# AJH_tides2_v40.net
KiCad netlist of a schematic drawn in EAGLE
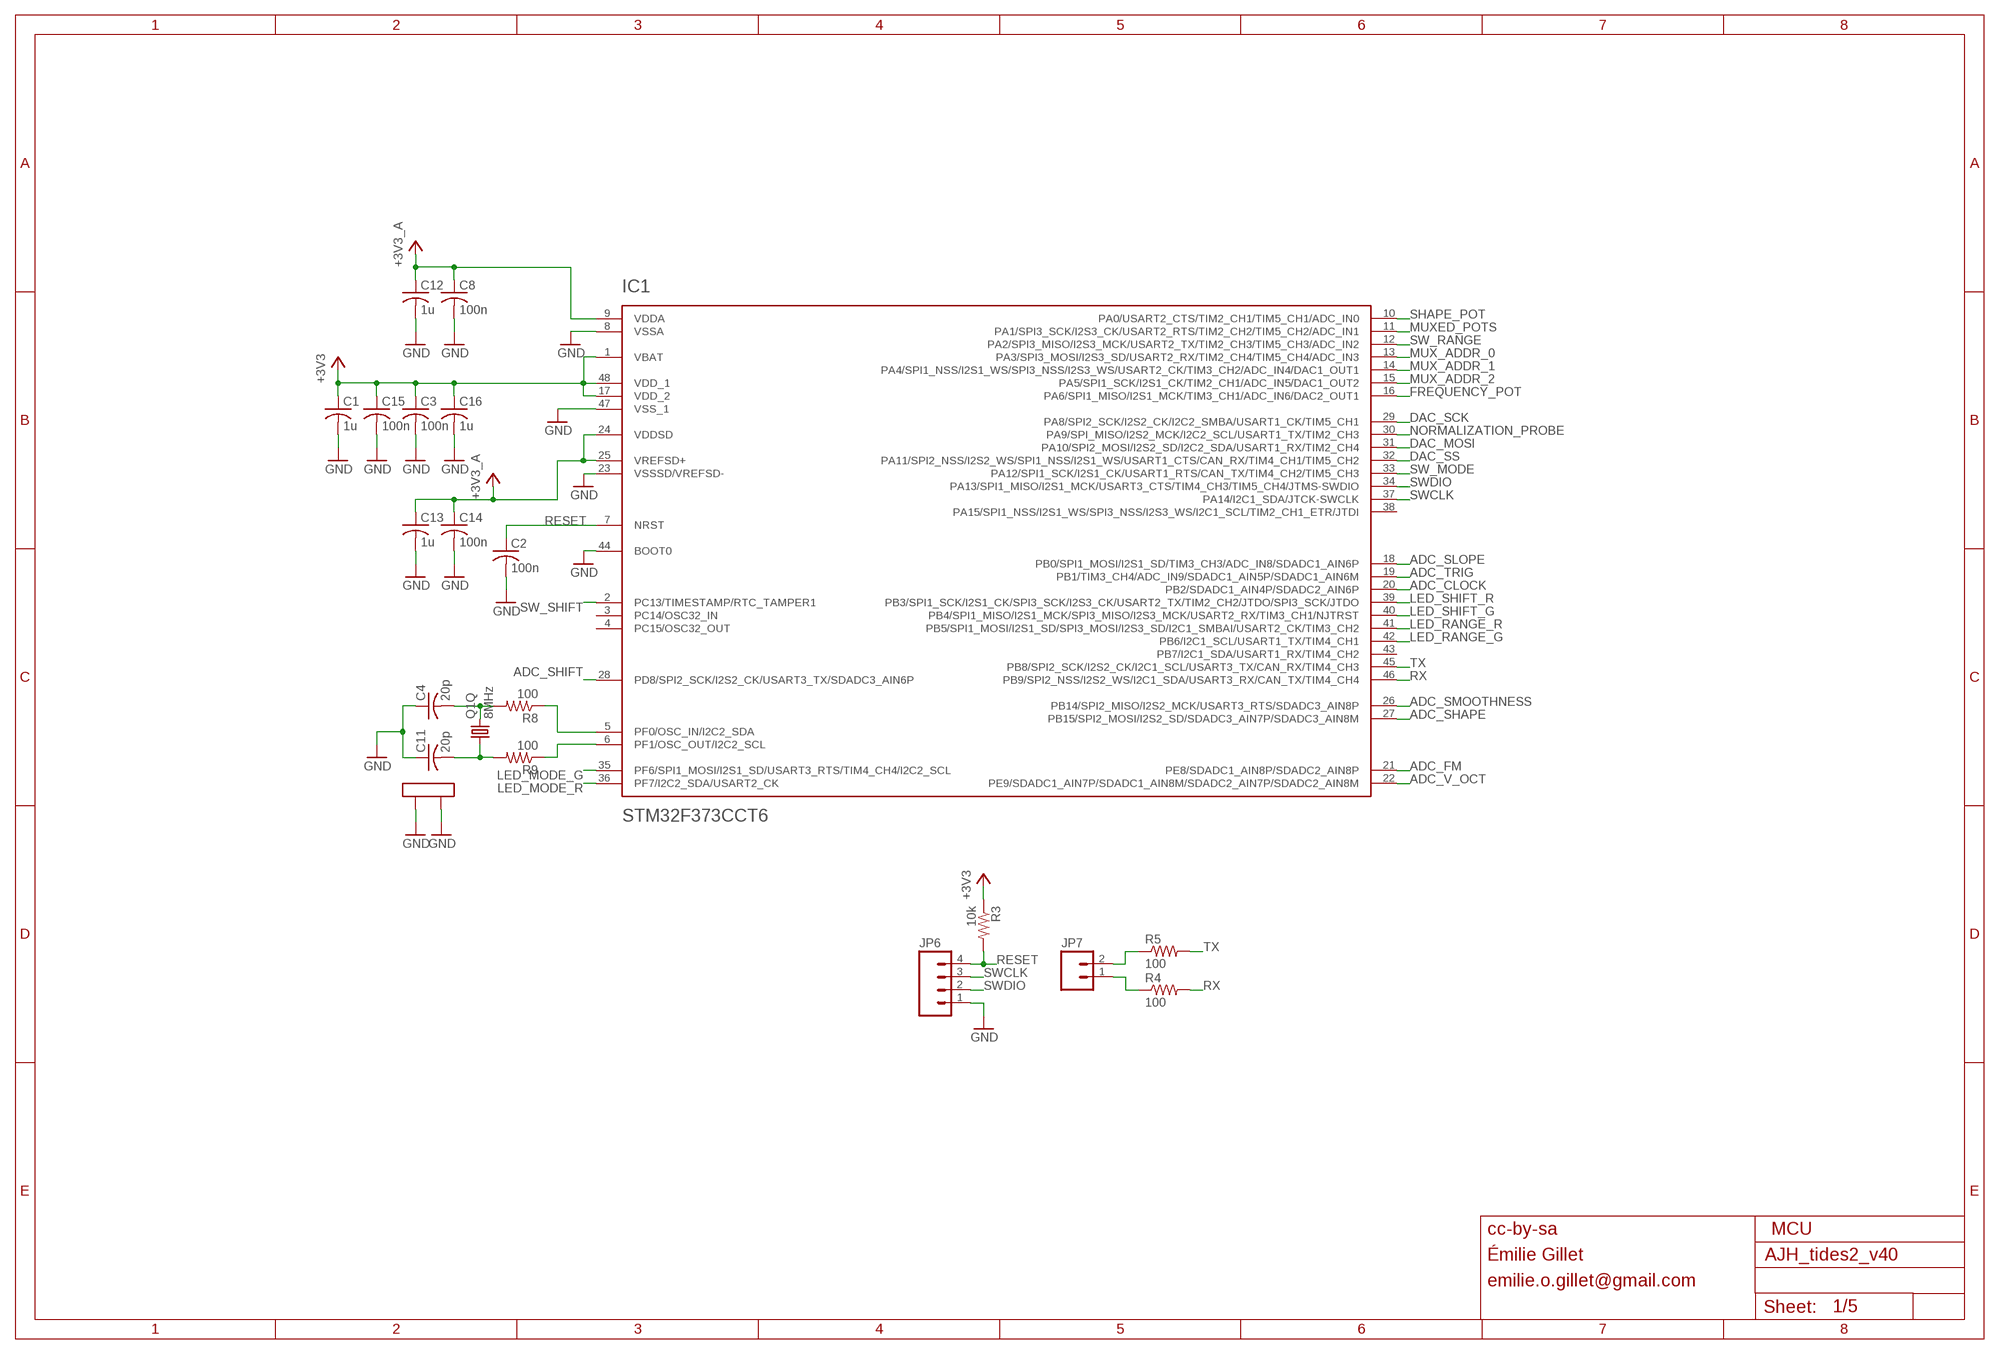
[diagram p0: schematic, sheet 1]
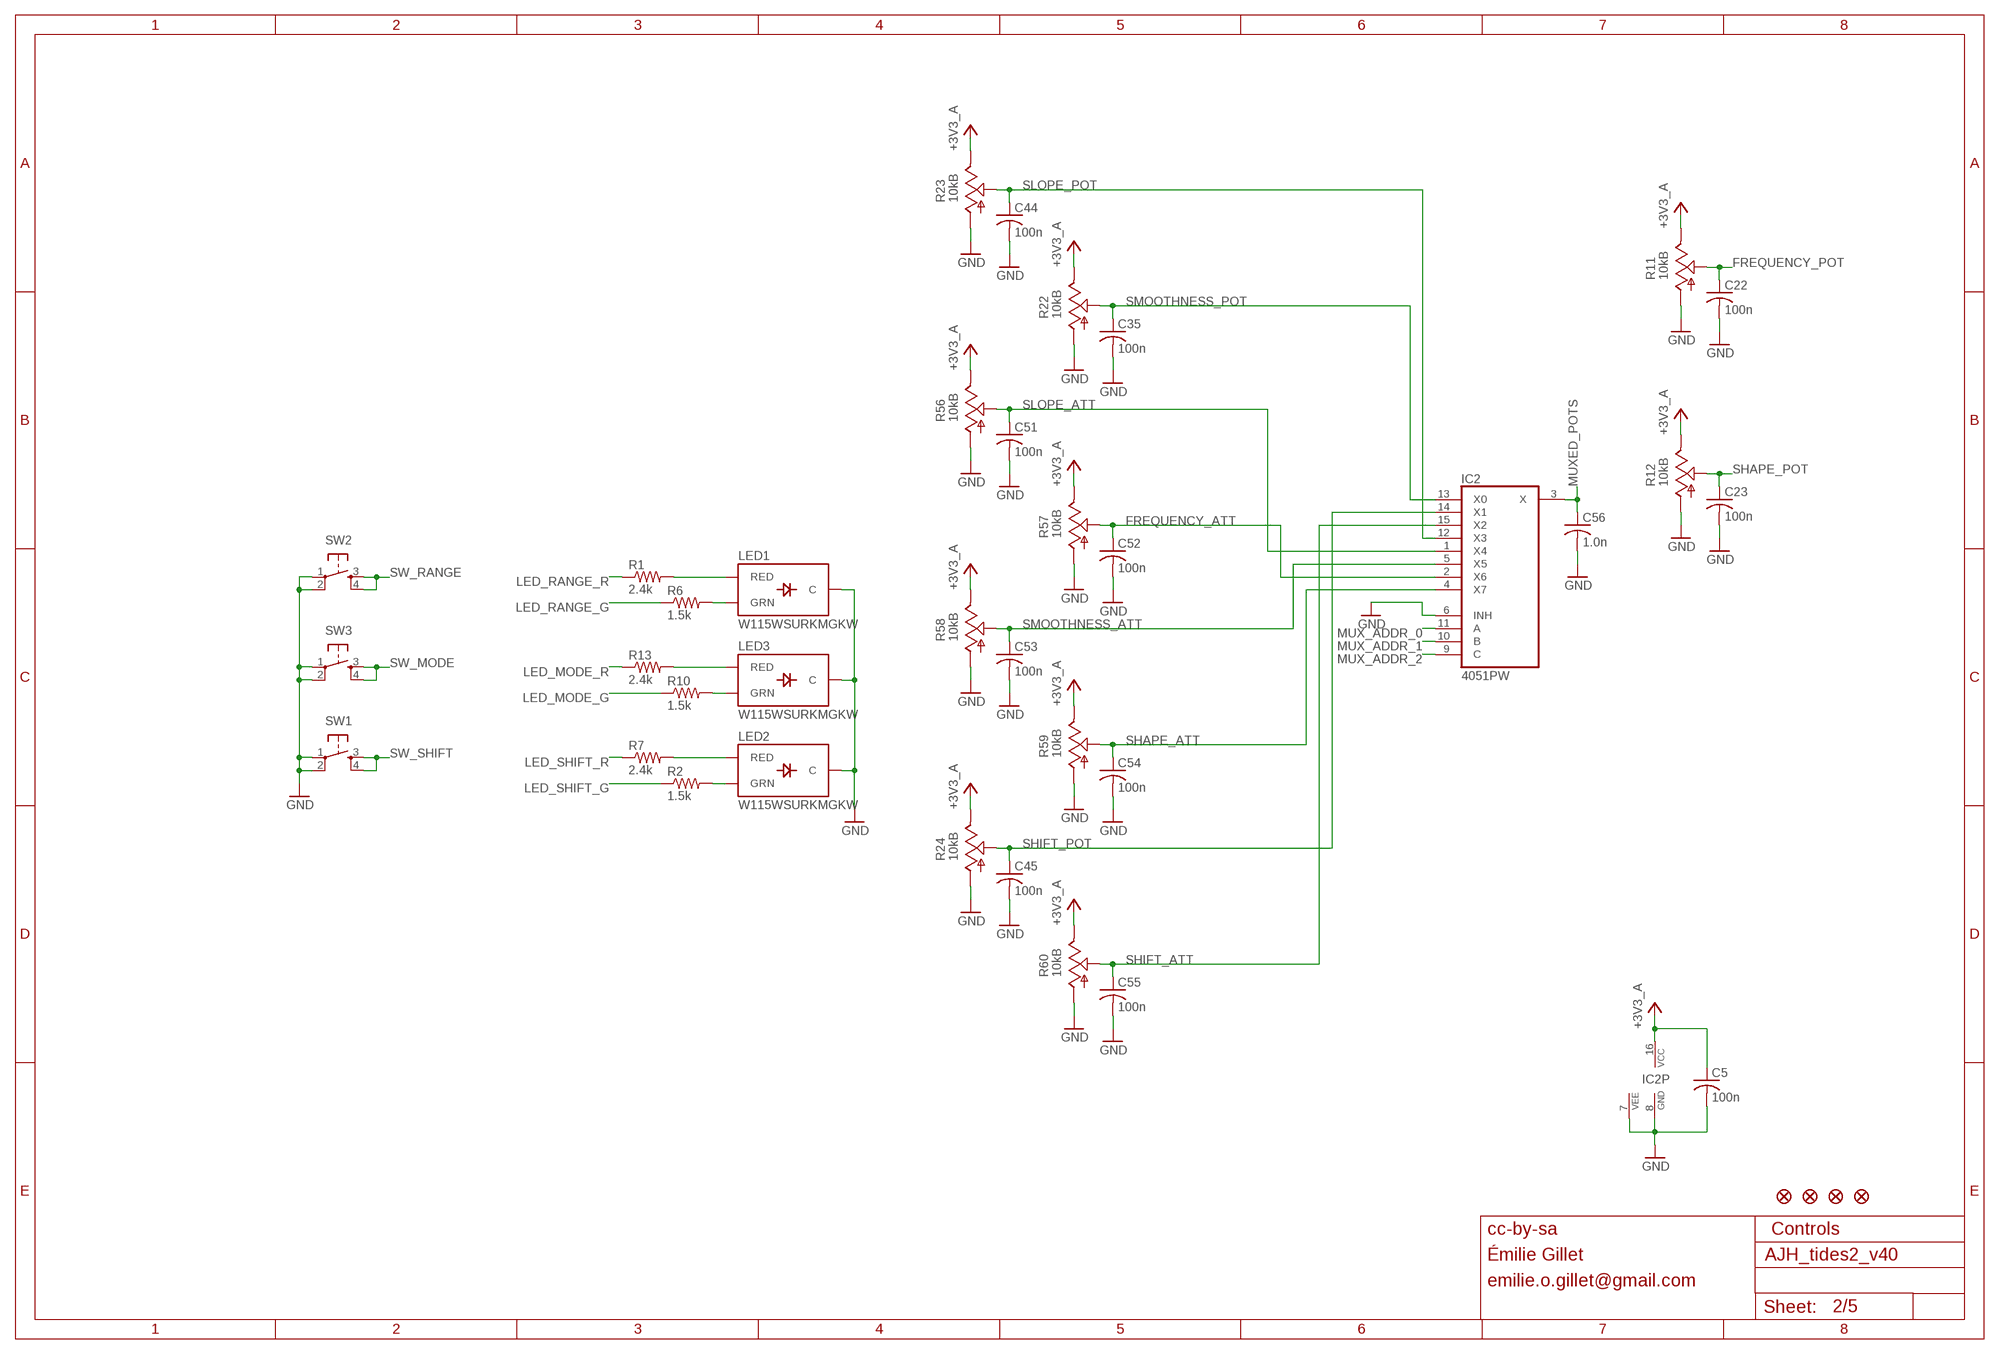
[diagram p1: schematic, sheet 2]
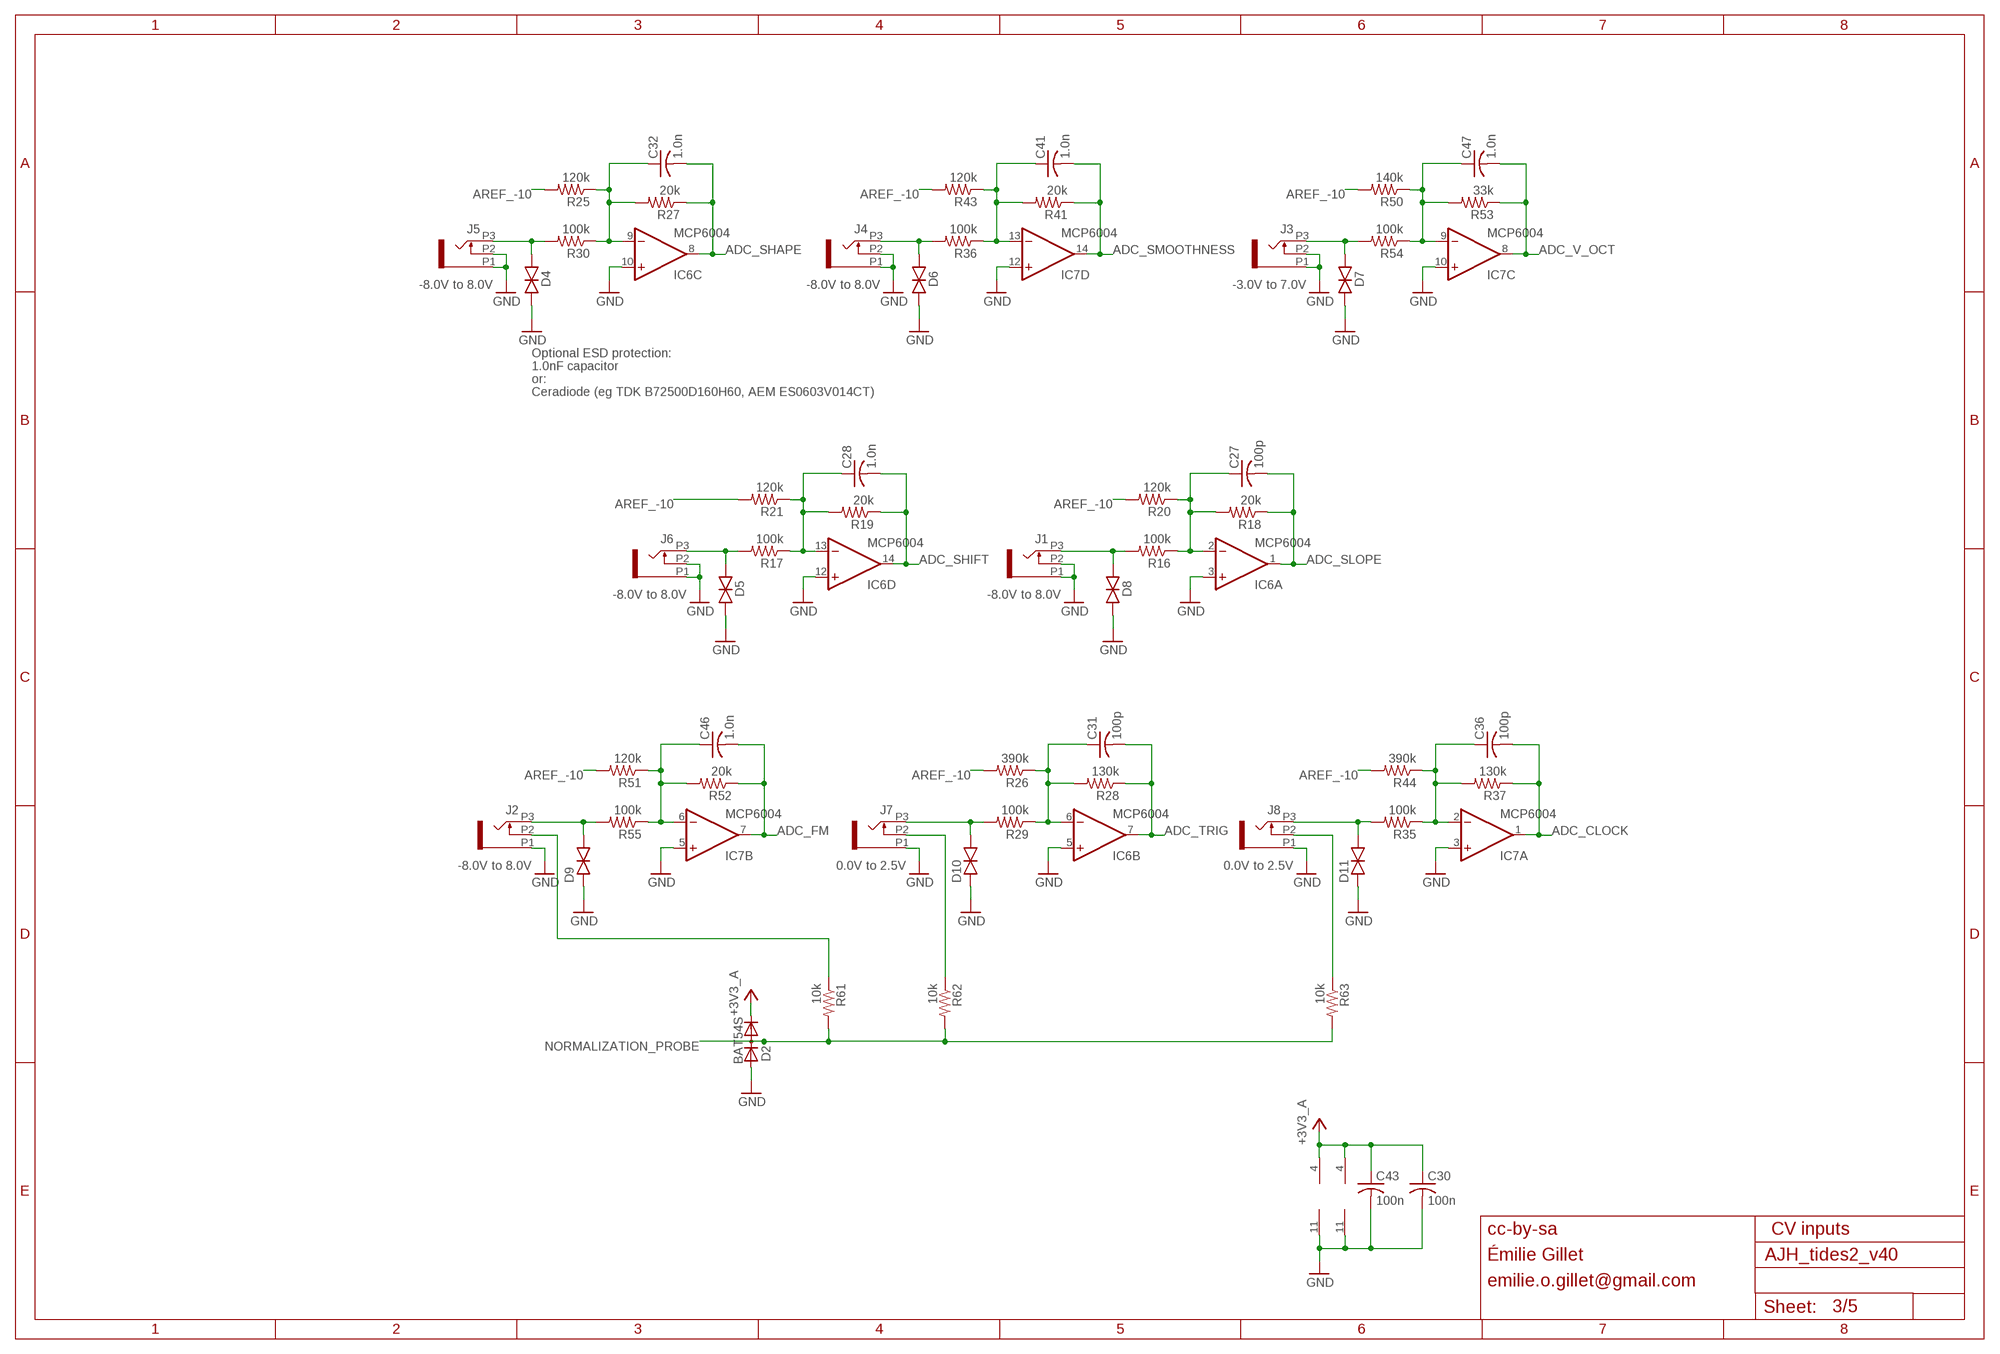
[diagram p2: schematic, sheet 3]
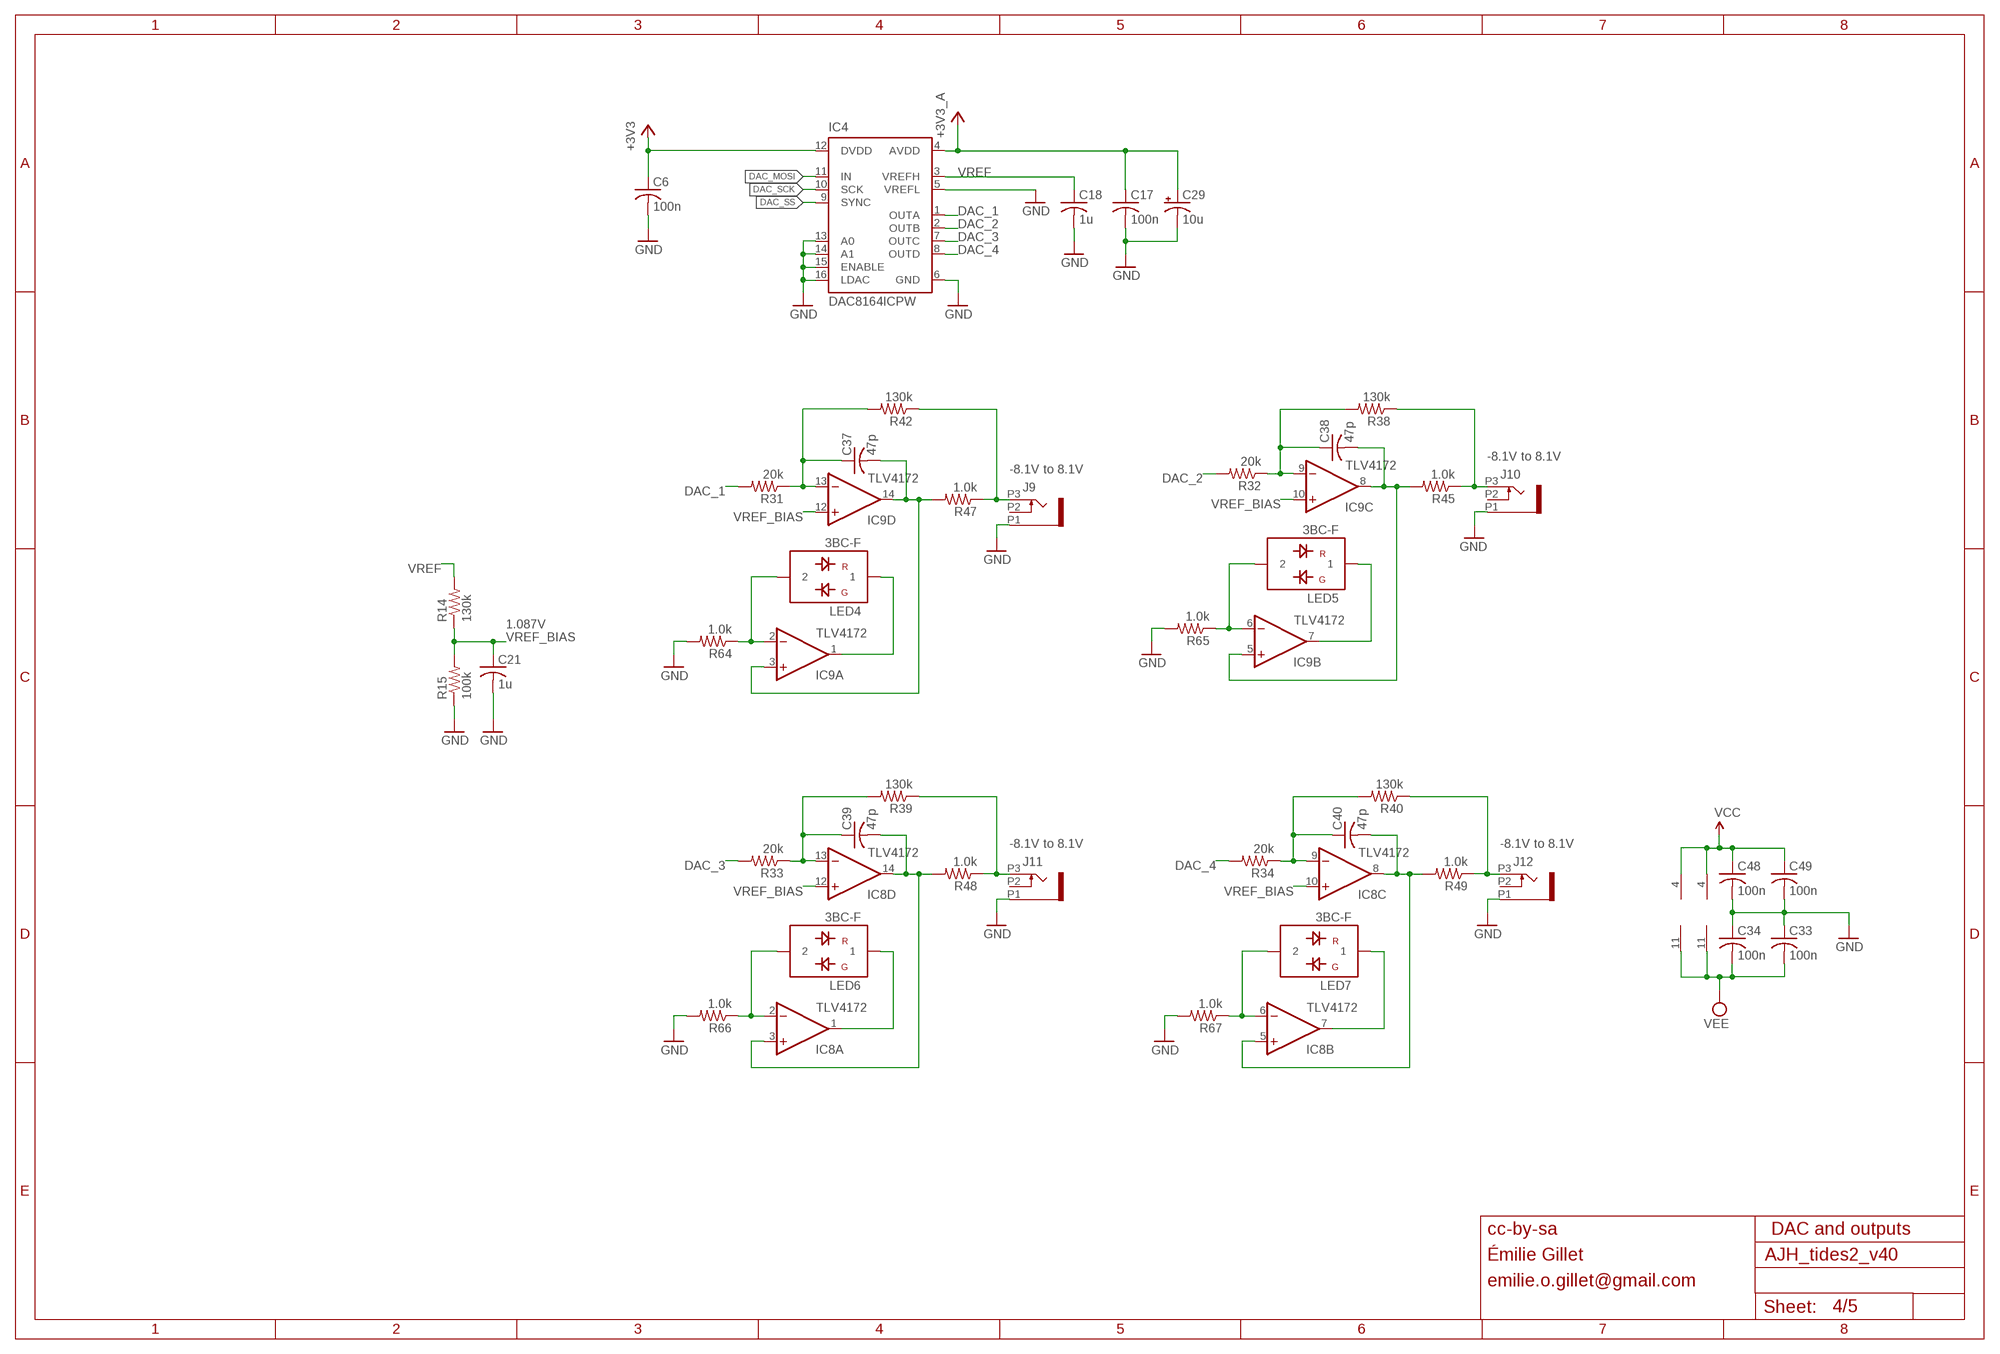
[diagram p3: schematic, sheet 4]
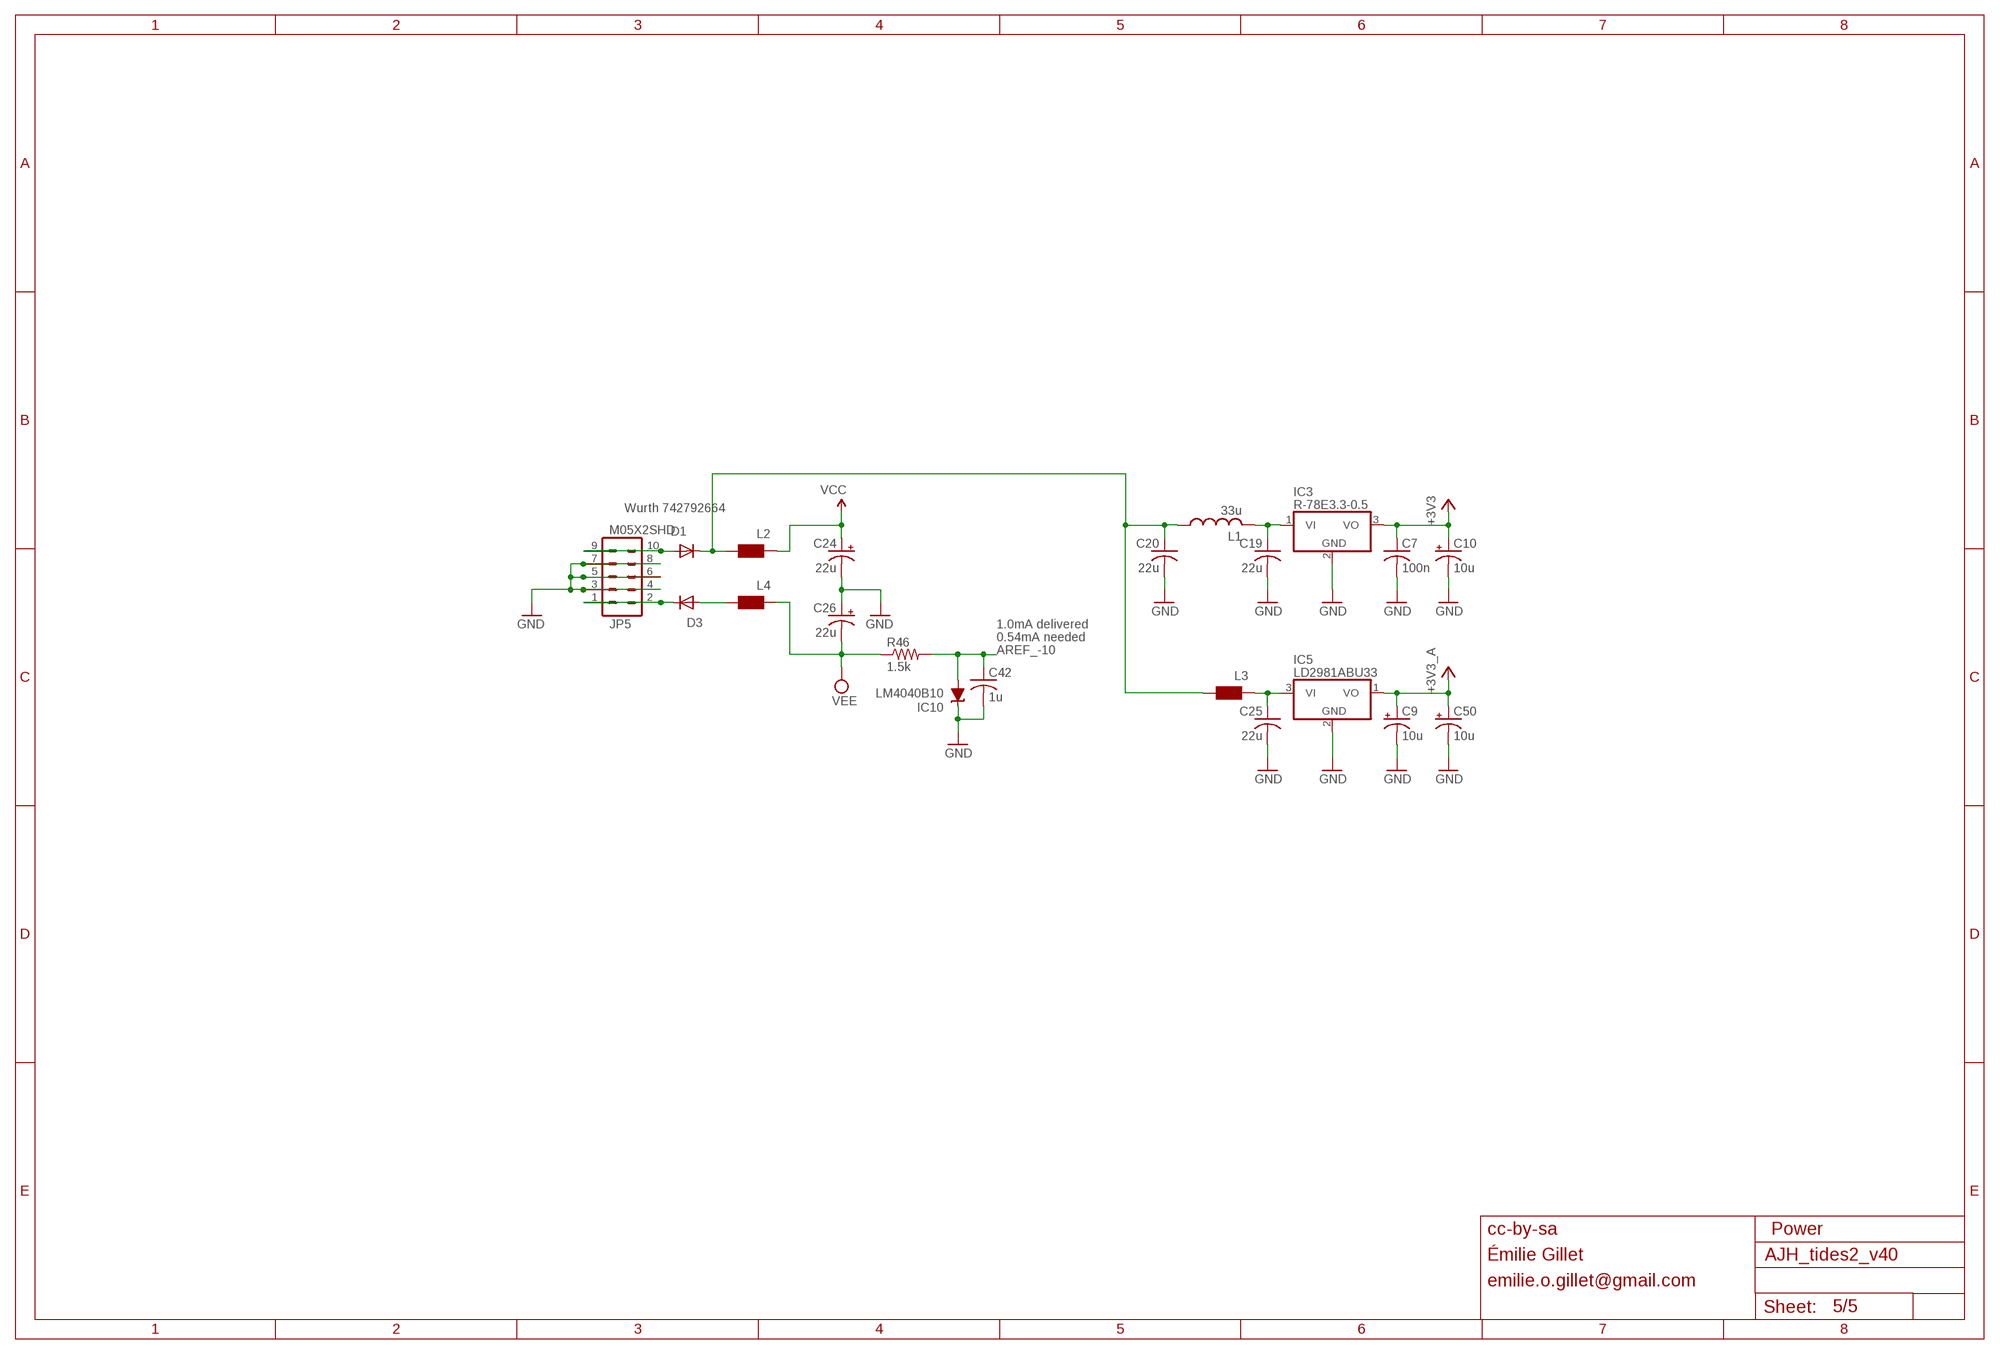
[diagram p4: schematic, sheet 5]

(export (version "E")
  (design (tool "Eeschema 10.0.6"))
  (components
    (comp (ref "C6")
      (value "100n")
      (footprint "eagle-import:C0402")
      (libsource (lib "eagle-import") (part "C-USC0402"))
    )
    (comp (ref "C17")
      (value "100n")
      (footprint "eagle-import:C0402")
      (libsource (lib "eagle-import") (part "C-USC0402"))
    )
    (comp (ref "C18")
      (value "1u")
      (footprint "eagle-import:C0402")
      (libsource (lib "eagle-import") (part "C-USC0402"))
    )
    (comp (ref "C21")
      (value "1u")
      (footprint "eagle-import:C0402")
      (libsource (lib "eagle-import") (part "C-USC0402"))
    )
    (comp (ref "C29")
      (value "10u")
      (footprint "eagle-import:PANASONIC_A")
      (libsource (lib "eagle-import") (part "CPOL-USA"))
    )
    (comp (ref "C33")
      (value "100n")
      (footprint "eagle-import:C0402")
      (libsource (lib "eagle-import") (part "C-USC0402"))
    )
    (comp (ref "C34")
      (value "100n")
      (footprint "eagle-import:C0402")
      (libsource (lib "eagle-import") (part "C-USC0402"))
    )
    (comp (ref "C37")
      (value "47p")
      (footprint "eagle-import:C0402")
      (libsource (lib "eagle-import") (part "C-USC0402"))
    )
    (comp (ref "C38")
      (value "47p")
      (footprint "eagle-import:C0402")
      (libsource (lib "eagle-import") (part "C-USC0402"))
    )
    (comp (ref "C39")
      (value "47p")
      (footprint "eagle-import:C0402")
      (libsource (lib "eagle-import") (part "C-USC0402"))
    )
    (comp (ref "C40")
      (value "47p")
      (footprint "eagle-import:C0402")
      (libsource (lib "eagle-import") (part "C-USC0402"))
    )
    (comp (ref "C48")
      (value "100n")
      (footprint "eagle-import:C0402")
      (libsource (lib "eagle-import") (part "C-USC0402"))
    )
    (comp (ref "C49")
      (value "100n")
      (footprint "eagle-import:C0402")
      (libsource (lib "eagle-import") (part "C-USC0402"))
    )
    (comp (ref "IC4")
      (value "DAC8164ICPW")
      (footprint "eagle-import:SOP65P640X110-16N")
      (libsource (lib "eagle-import") (part "DAC8564"))
    )
    (comp (ref "IC8")
      (value "TLV4172")
      (footprint "eagle-import:TSSOP14_065")
      (libsource (lib "eagle-import") (part "TL074PW"))
    )
    (comp (ref "IC9")
      (value "TLV4172")
      (footprint "eagle-import:TSSOP14_065")
      (libsource (lib "eagle-import") (part "TL074PW"))
    )
    (comp (ref "J9")
      (value "PJ301_THONKICONN6")
      (footprint "eagle-import:WQP_PJ_301M6")
      (libsource (lib "eagle-import") (part "PJ301_THONKICONN6"))
    )
    (comp (ref "J10")
      (value "PJ301_THONKICONN6")
      (footprint "eagle-import:WQP_PJ_301M6")
      (libsource (lib "eagle-import") (part "PJ301_THONKICONN6"))
    )
    (comp (ref "J11")
      (value "PJ301_THONKICONN6")
      (footprint "eagle-import:WQP_PJ_301M6")
      (libsource (lib "eagle-import") (part "PJ301_THONKICONN6"))
    )
    (comp (ref "J12")
      (value "PJ301_THONKICONN6")
      (footprint "eagle-import:WQP_PJ_301M6")
      (libsource (lib "eagle-import") (part "PJ301_THONKICONN6"))
    )
    (comp (ref "LED4")
      (value "3BC-F")
      (footprint "eagle-import:LED3MM")
      (libsource (lib "eagle-import") (part "LED-BICOLOR-SHARED-THROUGHHOLE"))
    )
    (comp (ref "LED5")
      (value "3BC-F")
      (footprint "eagle-import:LED3MM")
      (libsource (lib "eagle-import") (part "LED-BICOLOR-SHARED-THROUGHHOLE"))
    )
    (comp (ref "LED6")
      (value "3BC-F")
      (footprint "eagle-import:LED3MM")
      (libsource (lib "eagle-import") (part "LED-BICOLOR-SHARED-THROUGHHOLE"))
    )
    (comp (ref "LED7")
      (value "3BC-F")
      (footprint "eagle-import:LED3MM")
      (libsource (lib "eagle-import") (part "LED-BICOLOR-SHARED-THROUGHHOLE"))
    )
    (comp (ref "R14")
      (value "130k")
      (footprint "eagle-import:R0402")
      (libsource (lib "eagle-import") (part "R-US_R0402"))
    )
    (comp (ref "R15")
      (value "100k")
      (footprint "eagle-import:R0402")
      (libsource (lib "eagle-import") (part "R-US_R0402"))
    )
    (comp (ref "R31")
      (value "20k")
      (footprint "eagle-import:R0402")
      (libsource (lib "eagle-import") (part "R-US_R0402"))
    )
    (comp (ref "R32")
      (value "20k")
      (footprint "eagle-import:R0402")
      (libsource (lib "eagle-import") (part "R-US_R0402"))
    )
    (comp (ref "R33")
      (value "20k")
      (footprint "eagle-import:R0402")
      (libsource (lib "eagle-import") (part "R-US_R0402"))
    )
    (comp (ref "R34")
      (value "20k")
      (footprint "eagle-import:R0402")
      (libsource (lib "eagle-import") (part "R-US_R0402"))
    )
    (comp (ref "R38")
      (value "130k")
      (footprint "eagle-import:R0402")
      (libsource (lib "eagle-import") (part "R-US_R0402"))
    )
    (comp (ref "R39")
      (value "130k")
      (footprint "eagle-import:R0402")
      (libsource (lib "eagle-import") (part "R-US_R0402"))
    )
    (comp (ref "R40")
      (value "130k")
      (footprint "eagle-import:R0402")
      (libsource (lib "eagle-import") (part "R-US_R0402"))
    )
    (comp (ref "R42")
      (value "130k")
      (footprint "eagle-import:R0402")
      (libsource (lib "eagle-import") (part "R-US_R0402"))
    )
    (comp (ref "R45")
      (value "1.0k")
      (footprint "eagle-import:R0603")
      (libsource (lib "eagle-import") (part "R-US_R0603"))
    )
    (comp (ref "R47")
      (value "1.0k")
      (footprint "eagle-import:R0603")
      (libsource (lib "eagle-import") (part "R-US_R0603"))
    )
    (comp (ref "R48")
      (value "1.0k")
      (footprint "eagle-import:R0603")
      (libsource (lib "eagle-import") (part "R-US_R0603"))
    )
    (comp (ref "R49")
      (value "1.0k")
      (footprint "eagle-import:R0603")
      (libsource (lib "eagle-import") (part "R-US_R0603"))
    )
    (comp (ref "R64")
      (value "1.0k")
      (footprint "eagle-import:R0402")
      (libsource (lib "eagle-import") (part "R-US_R0402"))
    )
    (comp (ref "R65")
      (value "1.0k")
      (footprint "eagle-import:R0402")
      (libsource (lib "eagle-import") (part "R-US_R0402"))
    )
    (comp (ref "R66")
      (value "1.0k")
      (footprint "eagle-import:R0402")
      (libsource (lib "eagle-import") (part "R-US_R0402"))
    )
    (comp (ref "R67")
      (value "1.0k")
      (footprint "eagle-import:R0402")
      (libsource (lib "eagle-import") (part "R-US_R0402"))
    )
    (comp (ref "C7")
      (value "100n")
      (footprint "eagle-import:C0402")
      (libsource (lib "eagle-import") (part "C-USC0402"))
    )
    (comp (ref "C9")
      (value "10u")
      (footprint "eagle-import:PANASONIC_A")
      (libsource (lib "eagle-import") (part "CPOL-USA"))
    )
    (comp (ref "C10")
      (value "10u")
      (footprint "eagle-import:PANASONIC_A")
      (libsource (lib "eagle-import") (part "CPOL-USA"))
    )
    (comp (ref "C19")
      (value "22u")
      (footprint "eagle-import:C1206")
      (libsource (lib "eagle-import") (part "C-USC1206"))
    )
    (comp (ref "C20")
      (value "22u")
      (footprint "eagle-import:C1206")
      (libsource (lib "eagle-import") (part "C-USC1206"))
    )
    (comp (ref "C24")
      (value "22u")
      (footprint "eagle-import:PANASONIC_B")
      (libsource (lib "eagle-import") (part "CPOL-USB"))
    )
    (comp (ref "C25")
      (value "22u")
      (footprint "eagle-import:C1206")
      (libsource (lib "eagle-import") (part "C-USC1206"))
    )
    (comp (ref "C26")
      (value "22u")
      (footprint "eagle-import:PANASONIC_B")
      (libsource (lib "eagle-import") (part "CPOL-USB"))
    )
    (comp (ref "C42")
      (value "1u")
      (footprint "eagle-import:C0402")
      (libsource (lib "eagle-import") (part "C-USC0402"))
    )
    (comp (ref "C50")
      (value "10u")
      (footprint "eagle-import:PANASONIC_A")
      (libsource (lib "eagle-import") (part "CPOL-USA"))
    )
    (comp (ref "D1")
      (value "1N5819HW")
      (footprint "eagle-import:SOD123")
      (libsource (lib "eagle-import") (part "DIODE-SOD123"))
    )
    (comp (ref "D3")
      (value "1N5819HW")
      (footprint "eagle-import:SOD123")
      (libsource (lib "eagle-import") (part "DIODE-SOD123"))
    )
    (comp (ref "IC3")
      (value "R-78E3.3-0.5")
      (footprint "eagle-import:WE78")
      (libsource (lib "eagle-import") (part "WE173950378"))
    )
    (comp (ref "IC5")
      (value "LD2981ABU33")
      (footprint "eagle-import:SOT89")
      (libsource (lib "eagle-import") (part "LD2981ABU"))
    )
    (comp (ref "IC10")
      (value "LM4040B10")
      (footprint "eagle-import:DBZ_R-PDSO-G3")
      (libsource (lib "eagle-import") (part "LM4041DBZB12"))
    )
    (comp (ref "JP5")
      (value "M05X2SHD")
      (footprint "eagle-import:2X5-SHROUDED")
      (libsource (lib "eagle-import") (part "M05X2SHD"))
    )
    (comp (ref "L1")
      (value "33u")
      (footprint "eagle-import:L2012C")
      (libsource (lib "eagle-import") (part "L-USL2012C"))
    )
    (comp (ref "L2")
      (value "WE-CBF_0603")
      (footprint "eagle-import:0603")
      (libsource (lib "eagle-import") (part "WE-CBF_0603"))
    )
    (comp (ref "L3")
      (value "WE-CBF_0603")
      (footprint "eagle-import:0603")
      (libsource (lib "eagle-import") (part "WE-CBF_0603"))
    )
    (comp (ref "L4")
      (value "WE-CBF_0603")
      (footprint "eagle-import:0603")
      (libsource (lib "eagle-import") (part "WE-CBF_0603"))
    )
    (comp (ref "R46")
      (value "1.5k")
      (footprint "eagle-import:R0402")
      (libsource (lib "eagle-import") (part "R-US_R0402"))
    )
    (comp (ref "C27")
      (value "100p")
      (footprint "eagle-import:C0402")
      (libsource (lib "eagle-import") (part "C-USC0402"))
    )
    (comp (ref "C28")
      (value "1.0n")
      (footprint "eagle-import:C0402")
      (libsource (lib "eagle-import") (part "C-USC0402"))
    )
    (comp (ref "C30")
      (value "100n")
      (footprint "eagle-import:C0402")
      (libsource (lib "eagle-import") (part "C-USC0402"))
    )
    (comp (ref "C31")
      (value "100p")
      (footprint "eagle-import:C0402")
      (libsource (lib "eagle-import") (part "C-USC0402"))
    )
    (comp (ref "C32")
      (value "1.0n")
      (footprint "eagle-import:C0402")
      (libsource (lib "eagle-import") (part "C-USC0402"))
    )
    (comp (ref "C36")
      (value "100p")
      (footprint "eagle-import:C0402")
      (libsource (lib "eagle-import") (part "C-USC0402"))
    )
    (comp (ref "C41")
      (value "1.0n")
      (footprint "eagle-import:C0402")
      (libsource (lib "eagle-import") (part "C-USC0402"))
    )
    (comp (ref "C43")
      (value "100n")
      (footprint "eagle-import:C0402")
      (libsource (lib "eagle-import") (part "C-USC0402"))
    )
    (comp (ref "C46")
      (value "1.0n")
      (footprint "eagle-import:C0402")
      (libsource (lib "eagle-import") (part "C-USC0402"))
    )
    (comp (ref "C47")
      (value "1.0n")
      (footprint "eagle-import:C0402")
      (libsource (lib "eagle-import") (part "C-USC0402"))
    )
    (comp (ref "D2")
      (value "BAT54S")
      (footprint "eagle-import:SOT23")
      (libsource (lib "eagle-import") (part "DIODE_2CACA-SOT23"))
    )
    (comp (ref "D4")
      (value "TVS")
      (footprint "eagle-import:0603")
      (libsource (lib "eagle-import") (part "TVS"))
    )
    (comp (ref "D5")
      (value "TVS")
      (footprint "eagle-import:0603")
      (libsource (lib "eagle-import") (part "TVS"))
    )
    (comp (ref "D6")
      (value "TVS")
      (footprint "eagle-import:0603")
      (libsource (lib "eagle-import") (part "TVS"))
    )
    (comp (ref "D7")
      (value "TVS")
      (footprint "eagle-import:0603")
      (libsource (lib "eagle-import") (part "TVS"))
    )
    (comp (ref "D8")
      (value "TVS")
      (footprint "eagle-import:0603")
      (libsource (lib "eagle-import") (part "TVS"))
    )
    (comp (ref "D9")
      (value "TVS")
      (footprint "eagle-import:0603")
      (libsource (lib "eagle-import") (part "TVS"))
    )
    (comp (ref "D10")
      (value "TVS")
      (footprint "eagle-import:0603")
      (libsource (lib "eagle-import") (part "TVS"))
    )
    (comp (ref "D11")
      (value "TVS")
      (footprint "eagle-import:0603")
      (libsource (lib "eagle-import") (part "TVS"))
    )
    (comp (ref "IC6")
      (value "MCP6004")
      (footprint "eagle-import:TSSOP14_065")
      (libsource (lib "eagle-import") (part "TL074PW"))
    )
    (comp (ref "IC7")
      (value "MCP6004")
      (footprint "eagle-import:TSSOP14_065")
      (libsource (lib "eagle-import") (part "TL074PW"))
    )
    (comp (ref "J1")
      (value "PJ301_THONKICONN6")
      (footprint "eagle-import:WQP_PJ_301M6")
      (libsource (lib "eagle-import") (part "og-pj301_variations_PJ301_THONKICONN6"))
    )
    (comp (ref "J2")
      (value "PJ301_THONKICONN6")
      (footprint "eagle-import:WQP_PJ_301M6")
      (libsource (lib "eagle-import") (part "og-pj301_variations_PJ301_THONKICONN6"))
    )
    (comp (ref "J3")
      (value "PJ301_THONKICONN6")
      (footprint "eagle-import:WQP_PJ_301M6")
      (libsource (lib "eagle-import") (part "og-pj301_variations_PJ301_THONKICONN6"))
    )
    (comp (ref "J4")
      (value "PJ301_THONKICONN6")
      (footprint "eagle-import:WQP_PJ_301M6")
      (libsource (lib "eagle-import") (part "og-pj301_variations_PJ301_THONKICONN6"))
    )
    (comp (ref "J5")
      (value "PJ301_THONKICONN6")
      (footprint "eagle-import:WQP_PJ_301M6")
      (libsource (lib "eagle-import") (part "og-pj301_variations_PJ301_THONKICONN6"))
    )
    (comp (ref "J6")
      (value "PJ301_THONKICONN6")
      (footprint "eagle-import:WQP_PJ_301M6")
      (libsource (lib "eagle-import") (part "og-pj301_variations_PJ301_THONKICONN6"))
    )
    (comp (ref "J7")
      (value "PJ301_THONKICONN6")
      (footprint "eagle-import:WQP_PJ_301M6")
      (libsource (lib "eagle-import") (part "og-pj301_variations_PJ301_THONKICONN6"))
    )
    (comp (ref "J8")
      (value "PJ301_THONKICONN6")
      (footprint "eagle-import:WQP_PJ_301M6")
      (libsource (lib "eagle-import") (part "og-pj301_variations_PJ301_THONKICONN6"))
    )
    (comp (ref "R16")
      (value "100k")
      (footprint "eagle-import:R0402")
      (libsource (lib "eagle-import") (part "R-US_R0402"))
    )
    (comp (ref "R17")
      (value "100k")
      (footprint "eagle-import:R0402")
      (libsource (lib "eagle-import") (part "R-US_R0402"))
    )
    (comp (ref "R18")
      (value "20k")
      (footprint "eagle-import:R0402")
      (libsource (lib "eagle-import") (part "R-US_R0402"))
    )
    (comp (ref "R19")
      (value "20k")
      (footprint "eagle-import:R0402")
      (libsource (lib "eagle-import") (part "R-US_R0402"))
    )
    (comp (ref "R20")
      (value "120k")
      (footprint "eagle-import:R0402")
      (libsource (lib "eagle-import") (part "R-US_R0402"))
    )
    (comp (ref "R21")
      (value "120k")
      (footprint "eagle-import:R0402")
      (libsource (lib "eagle-import") (part "R-US_R0402"))
    )
    (comp (ref "R25")
      (value "120k")
      (footprint "eagle-import:R0402")
      (libsource (lib "eagle-import") (part "R-US_R0402"))
    )
    (comp (ref "R26")
      (value "390k")
      (footprint "eagle-import:R0402")
      (libsource (lib "eagle-import") (part "R-US_R0402"))
    )
    (comp (ref "R27")
      (value "20k")
      (footprint "eagle-import:R0402")
      (libsource (lib "eagle-import") (part "R-US_R0402"))
    )
    (comp (ref "R28")
      (value "130k")
      (footprint "eagle-import:R0402")
      (libsource (lib "eagle-import") (part "R-US_R0402"))
    )
    (comp (ref "R29")
      (value "100k")
      (footprint "eagle-import:R0402")
      (libsource (lib "eagle-import") (part "R-US_R0402"))
    )
    (comp (ref "R30")
      (value "100k")
      (footprint "eagle-import:R0402")
      (libsource (lib "eagle-import") (part "R-US_R0402"))
    )
    (comp (ref "R35")
      (value "100k")
      (footprint "eagle-import:R0402")
      (libsource (lib "eagle-import") (part "R-US_R0402"))
    )
    (comp (ref "R36")
      (value "100k")
      (footprint "eagle-import:R0402")
      (libsource (lib "eagle-import") (part "R-US_R0402"))
    )
    (comp (ref "R37")
      (value "130k")
      (footprint "eagle-import:R0402")
      (libsource (lib "eagle-import") (part "R-US_R0402"))
    )
    (comp (ref "R41")
      (value "20k")
      (footprint "eagle-import:R0402")
      (libsource (lib "eagle-import") (part "R-US_R0402"))
    )
    (comp (ref "R43")
      (value "120k")
      (footprint "eagle-import:R0402")
      (libsource (lib "eagle-import") (part "R-US_R0402"))
    )
    (comp (ref "R44")
      (value "390k")
      (footprint "eagle-import:R0402")
      (libsource (lib "eagle-import") (part "R-US_R0402"))
    )
    (comp (ref "R50")
      (value "140k")
      (footprint "eagle-import:R0402")
      (libsource (lib "eagle-import") (part "R-US_R0402"))
    )
    (comp (ref "R51")
      (value "120k")
      (footprint "eagle-import:R0402")
      (libsource (lib "eagle-import") (part "R-US_R0402"))
    )
    (comp (ref "R52")
      (value "20k")
      (footprint "eagle-import:R0402")
      (libsource (lib "eagle-import") (part "R-US_R0402"))
    )
    (comp (ref "R53")
      (value "33k")
      (footprint "eagle-import:R0402")
      (libsource (lib "eagle-import") (part "R-US_R0402"))
    )
    (comp (ref "R54")
      (value "100k")
      (footprint "eagle-import:R0402")
      (libsource (lib "eagle-import") (part "R-US_R0402"))
    )
    (comp (ref "R55")
      (value "100k")
      (footprint "eagle-import:R0402")
      (libsource (lib "eagle-import") (part "R-US_R0402"))
    )
    (comp (ref "R61")
      (value "10k")
      (footprint "eagle-import:R0402")
      (libsource (lib "eagle-import") (part "R-US_R0402"))
    )
    (comp (ref "R62")
      (value "10k")
      (footprint "eagle-import:R0402")
      (libsource (lib "eagle-import") (part "R-US_R0402"))
    )
    (comp (ref "R63")
      (value "10k")
      (footprint "eagle-import:R0402")
      (libsource (lib "eagle-import") (part "R-US_R0402"))
    )
    (comp (ref "C5")
      (value "100n")
      (footprint "eagle-import:C0402")
      (libsource (lib "eagle-import") (part "C-USC0402"))
    )
    (comp (ref "C22")
      (value "100n")
      (footprint "eagle-import:C0402")
      (libsource (lib "eagle-import") (part "C-USC0402"))
    )
    (comp (ref "C23")
      (value "100n")
      (footprint "eagle-import:C0402")
      (libsource (lib "eagle-import") (part "C-USC0402"))
    )
    (comp (ref "C35")
      (value "100n")
      (footprint "eagle-import:C0402")
      (libsource (lib "eagle-import") (part "C-USC0402"))
    )
    (comp (ref "C44")
      (value "100n")
      (footprint "eagle-import:C0402")
      (libsource (lib "eagle-import") (part "C-USC0402"))
    )
    (comp (ref "C45")
      (value "100n")
      (footprint "eagle-import:C0402")
      (libsource (lib "eagle-import") (part "C-USC0402"))
    )
    (comp (ref "C51")
      (value "100n")
      (footprint "eagle-import:C0402")
      (libsource (lib "eagle-import") (part "C-USC0402"))
    )
    (comp (ref "C52")
      (value "100n")
      (footprint "eagle-import:C0402")
      (libsource (lib "eagle-import") (part "C-USC0402"))
    )
    (comp (ref "C53")
      (value "100n")
      (footprint "eagle-import:C0402")
      (libsource (lib "eagle-import") (part "C-USC0402"))
    )
    (comp (ref "C54")
      (value "100n")
      (footprint "eagle-import:C0402")
      (libsource (lib "eagle-import") (part "C-USC0402"))
    )
    (comp (ref "C55")
      (value "100n")
      (footprint "eagle-import:C0402")
      (libsource (lib "eagle-import") (part "C-USC0402"))
    )
    (comp (ref "C56")
      (value "1.0n")
      (footprint "eagle-import:C0402")
      (libsource (lib "eagle-import") (part "C-USC0402"))
    )
    (comp (ref "IC2")
      (value "4051PW")
      (footprint "eagle-import:TSSOP16_065")
      (libsource (lib "eagle-import") (part "4051PW"))
    )
    (comp (ref "JP1")
      (value "FIDUCIAL1X2")
      (footprint "eagle-import:FIDUCIAL-1X2")
      (libsource (lib "eagle-import") (part "FIDUCIAL1X2"))
    )
    (comp (ref "JP2")
      (value "FIDUCIAL1X2")
      (footprint "eagle-import:FIDUCIAL-1X2")
      (libsource (lib "eagle-import") (part "FIDUCIAL1X2"))
    )
    (comp (ref "JP3")
      (value "FIDUCIAL1X2")
      (footprint "eagle-import:FIDUCIAL-1X2")
      (libsource (lib "eagle-import") (part "FIDUCIAL1X2"))
    )
    (comp (ref "JP4")
      (value "FIDUCIAL1X2")
      (footprint "eagle-import:FIDUCIAL-1X2")
      (libsource (lib "eagle-import") (part "FIDUCIAL1X2"))
    )
    (comp (ref "LED1")
      (value "W115WSURKMGKW")
      (footprint "eagle-import:LED-BICOLOR-THROUGHHOLE-2.54")
      (libsource (lib "eagle-import") (part "LED-BICOLOR-THROUGHHOLE2.54"))
    )
    (comp (ref "LED2")
      (value "W115WSURKMGKW")
      (footprint "eagle-import:LED-BICOLOR-THROUGHHOLE-2.54")
      (libsource (lib "eagle-import") (part "LED-BICOLOR-THROUGHHOLE2.54"))
    )
    (comp (ref "LED3")
      (value "W115WSURKMGKW")
      (footprint "eagle-import:LED-BICOLOR-THROUGHHOLE-2.54")
      (libsource (lib "eagle-import") (part "LED-BICOLOR-THROUGHHOLE2.54"))
    )
    (comp (ref "R1")
      (value "2.4k")
      (footprint "eagle-import:R0402")
      (libsource (lib "eagle-import") (part "R-US_R0402"))
    )
    (comp (ref "R2")
      (value "1.5k")
      (footprint "eagle-import:R0402")
      (libsource (lib "eagle-import") (part "R-US_R0402"))
    )
    (comp (ref "R6")
      (value "1.5k")
      (footprint "eagle-import:R0402")
      (libsource (lib "eagle-import") (part "R-US_R0402"))
    )
    (comp (ref "R7")
      (value "2.4k")
      (footprint "eagle-import:R0402")
      (libsource (lib "eagle-import") (part "R-US_R0402"))
    )
    (comp (ref "R10")
      (value "1.5k")
      (footprint "eagle-import:R0402")
      (libsource (lib "eagle-import") (part "R-US_R0402"))
    )
    (comp (ref "R11")
      (value "10kB")
      (footprint "eagle-import:ALPS_POT_VERTICAL_PS")
      (libsource (lib "eagle-import") (part "POT_USVERTICAL_PS"))
    )
    (comp (ref "R12")
      (value "10kB")
      (footprint "eagle-import:ALPS_POT_VERTICAL_PS")
      (libsource (lib "eagle-import") (part "POT_USVERTICAL_PS"))
    )
    (comp (ref "R13")
      (value "2.4k")
      (footprint "eagle-import:R0402")
      (libsource (lib "eagle-import") (part "R-US_R0402"))
    )
    (comp (ref "R22")
      (value "10kB")
      (footprint "eagle-import:ALPS_POT_VERTICAL_PS")
      (libsource (lib "eagle-import") (part "POT_USVERTICAL_PS"))
    )
    (comp (ref "R23")
      (value "10kB")
      (footprint "eagle-import:ALPS_POT_VERTICAL_PS")
      (libsource (lib "eagle-import") (part "POT_USVERTICAL_PS"))
    )
    (comp (ref "R24")
      (value "10kB")
      (footprint "eagle-import:ALPS_POT_VERTICAL_PS")
      (libsource (lib "eagle-import") (part "POT_USVERTICAL_PS"))
    )
    (comp (ref "R56")
      (value "10kB")
      (footprint "eagle-import:ALPS_POT_VERTICAL")
      (libsource (lib "eagle-import") (part "POT_USVERTICAL"))
    )
    (comp (ref "R57")
      (value "10kB")
      (footprint "eagle-import:ALPS_POT_VERTICAL")
      (libsource (lib "eagle-import") (part "POT_USVERTICAL"))
    )
    (comp (ref "R58")
      (value "10kB")
      (footprint "eagle-import:ALPS_POT_VERTICAL")
      (libsource (lib "eagle-import") (part "POT_USVERTICAL"))
    )
    (comp (ref "R59")
      (value "10kB")
      (footprint "eagle-import:ALPS_POT_VERTICAL")
      (libsource (lib "eagle-import") (part "POT_USVERTICAL"))
    )
    (comp (ref "R60")
      (value "10kB")
      (footprint "eagle-import:ALPS_POT_VERTICAL")
      (libsource (lib "eagle-import") (part "POT_USVERTICAL"))
    )
    (comp (ref "SW1")
      (value "TAC_SWITCHPTH")
      (footprint "eagle-import:TACTILE-PTH")
      (libsource (lib "eagle-import") (part "TAC_SWITCHPTH"))
    )
    (comp (ref "SW2")
      (value "TAC_SWITCHPTH")
      (footprint "eagle-import:TACTILE-PTH")
      (libsource (lib "eagle-import") (part "TAC_SWITCHPTH"))
    )
    (comp (ref "SW3")
      (value "TAC_SWITCHPTH")
      (footprint "eagle-import:TACTILE-PTH")
      (libsource (lib "eagle-import") (part "TAC_SWITCHPTH"))
    )
    (comp (ref "C1")
      (value "1u")
      (footprint "eagle-import:C0402")
      (libsource (lib "eagle-import") (part "C-USC0402"))
    )
    (comp (ref "C2")
      (value "100n")
      (footprint "eagle-import:C0402")
      (libsource (lib "eagle-import") (part "C-USC0402"))
    )
    (comp (ref "C3")
      (value "100n")
      (footprint "eagle-import:C0402")
      (libsource (lib "eagle-import") (part "C-USC0402"))
    )
    (comp (ref "C4")
      (value "20p")
      (footprint "eagle-import:C0402")
      (libsource (lib "eagle-import") (part "C-USC0402"))
    )
    (comp (ref "C8")
      (value "100n")
      (footprint "eagle-import:C0402")
      (libsource (lib "eagle-import") (part "C-USC0402"))
    )
    (comp (ref "C11")
      (value "20p")
      (footprint "eagle-import:C0402")
      (libsource (lib "eagle-import") (part "C-USC0402"))
    )
    (comp (ref "C12")
      (value "1u")
      (footprint "eagle-import:C0402")
      (libsource (lib "eagle-import") (part "C-USC0402"))
    )
    (comp (ref "C13")
      (value "1u")
      (footprint "eagle-import:C0402")
      (libsource (lib "eagle-import") (part "C-USC0402"))
    )
    (comp (ref "C14")
      (value "100n")
      (footprint "eagle-import:C0402")
      (libsource (lib "eagle-import") (part "C-USC0402"))
    )
    (comp (ref "C15")
      (value "100n")
      (footprint "eagle-import:C0402")
      (libsource (lib "eagle-import") (part "C-USC0402"))
    )
    (comp (ref "C16")
      (value "1u")
      (footprint "eagle-import:C0402")
      (libsource (lib "eagle-import") (part "C-USC0402"))
    )
    (comp (ref "IC1")
      (value "STM32F373CCT6")
      (footprint "eagle-import:LQFP48")
      (libsource (lib "eagle-import") (part "STM32F373C"))
    )
    (comp (ref "JP6")
      (value "M04PTH")
      (footprint "eagle-import:1X04")
      (libsource (lib "eagle-import") (part "M04PTH"))
    )
    (comp (ref "JP7")
      (value "M02PTH")
      (footprint "eagle-import:1X02")
      (libsource (lib "eagle-import") (part "M02PTH"))
    )
    (comp (ref "Q1")
      (value "8MHz")
      (footprint "eagle-import:CTS406")
      (libsource (lib "eagle-import") (part "CRYSTAL"))
    )
    (comp (ref "R3")
      (value "10k")
      (footprint "eagle-import:R0402")
      (libsource (lib "eagle-import") (part "R-US_R0402"))
    )
    (comp (ref "R4")
      (value "100")
      (footprint "eagle-import:R0402")
      (libsource (lib "eagle-import") (part "R-US_R0402"))
    )
    (comp (ref "R5")
      (value "100")
      (footprint "eagle-import:R0402")
      (libsource (lib "eagle-import") (part "R-US_R0402"))
    )
    (comp (ref "R8")
      (value "100")
      (footprint "eagle-import:R0402")
      (libsource (lib "eagle-import") (part "R-US_R0402"))
    )
    (comp (ref "R9")
      (value "100")
      (footprint "eagle-import:R0402")
      (libsource (lib "eagle-import") (part "R-US_R0402"))
    )
  )
  (nets
    (net (code "1") (name "+3V3") (class "Default")
      (node (ref "C1") (pin "1") (pinfunction "1_1") (pintype "passive"))
      (node (ref "C10") (pin "+") (pinfunction "+_+") (pintype "passive"))
      (node (ref "C15") (pin "1") (pinfunction "1_1") (pintype "passive"))
      (node (ref "C16") (pin "1") (pinfunction "1_1") (pintype "passive"))
      (node (ref "C3") (pin "1") (pinfunction "1_1") (pintype "passive"))
      (node (ref "C6") (pin "1") (pinfunction "1_1") (pintype "passive"))
      (node (ref "C7") (pin "1") (pinfunction "1_1") (pintype "passive"))
      (node (ref "IC1") (pin "1") (pinfunction "VBAT_1") (pintype "power_in"))
      (node (ref "IC1") (pin "17") (pinfunction "VDD_2_17") (pintype "power_in"))
      (node (ref "IC1") (pin "48") (pinfunction "VDD_1_48") (pintype "power_in"))
      (node (ref "IC3") (pin "3") (pinfunction "VO_3") (pintype "passive"))
      (node (ref "IC4") (pin "12") (pinfunction "DVDD_12") (pintype "power_in"))
      (node (ref "R3") (pin "1") (pinfunction "1_1") (pintype "passive"))
    )
    (net (code "2") (name "+3V3_A") (class "Default")
      (node (ref "C12") (pin "1") (pinfunction "1_1") (pintype "passive"))
      (node (ref "C13") (pin "1") (pinfunction "1_1") (pintype "passive"))
      (node (ref "C14") (pin "1") (pinfunction "1_1") (pintype "passive"))
      (node (ref "C17") (pin "1") (pinfunction "1_1") (pintype "passive"))
      (node (ref "C29") (pin "+") (pinfunction "+_+") (pintype "passive"))
      (node (ref "C30") (pin "1") (pinfunction "1_1") (pintype "passive"))
      (node (ref "C43") (pin "1") (pinfunction "1_1") (pintype "passive"))
      (node (ref "C5") (pin "1") (pinfunction "1_1") (pintype "passive"))
      (node (ref "C50") (pin "+") (pinfunction "+_+") (pintype "passive"))
      (node (ref "C8") (pin "1") (pinfunction "1_1") (pintype "passive"))
      (node (ref "C9") (pin "+") (pinfunction "+_+") (pintype "passive"))
      (node (ref "D2") (pin "2") (pinfunction "C_2") (pintype "passive"))
      (node (ref "IC1") (pin "24") (pinfunction "VDDSD_24") (pintype "power_in"))
      (node (ref "IC1") (pin "25") (pinfunction "VREFSD+_25") (pintype "power_in"))
      (node (ref "IC1") (pin "9") (pinfunction "VDDA_9") (pintype "power_in"))
      (node (ref "IC2") (pin "16") (pinfunction "VCC_16") (pintype "power_in"))
      (node (ref "IC4") (pin "4") (pinfunction "AVDD_4") (pintype "power_in"))
      (node (ref "IC5") (pin "1") (pinfunction "VO_1") (pintype "passive"))
      (node (ref "IC6") (pin "4") (pinfunction "V+_4") (pintype "power_in"))
      (node (ref "IC7") (pin "4") (pinfunction "V+_4") (pintype "power_in"))
      (node (ref "R11") (pin "P$1") (pinfunction "E_P$1") (pintype "passive"))
      (node (ref "R12") (pin "P$1") (pinfunction "E_P$1") (pintype "passive"))
      (node (ref "R22") (pin "P$1") (pinfunction "E_P$1") (pintype "passive"))
      (node (ref "R23") (pin "P$1") (pinfunction "E_P$1") (pintype "passive"))
      (node (ref "R24") (pin "P$1") (pinfunction "E_P$1") (pintype "passive"))
      (node (ref "R56") (pin "P$1") (pinfunction "E_P$1") (pintype "passive"))
      (node (ref "R57") (pin "P$1") (pinfunction "E_P$1") (pintype "passive"))
      (node (ref "R58") (pin "P$1") (pinfunction "E_P$1") (pintype "passive"))
      (node (ref "R59") (pin "P$1") (pinfunction "E_P$1") (pintype "passive"))
      (node (ref "R60") (pin "P$1") (pinfunction "E_P$1") (pintype "passive"))
    )
    (net (code "3") (name "ADC_CLOCK") (class "Default")
      (node (ref "C36") (pin "2") (pinfunction "2_2") (pintype "passive"))
      (node (ref "IC1") (pin "20") (pinfunction "PB2/SDADC1_AIN4P/SDADC2_AIN6P_20") (pintype "bidirectional"))
      (node (ref "IC7") (pin "1") (pinfunction "OUT_1") (pintype "output"))
      (node (ref "R37") (pin "1") (pinfunction "1_1") (pintype "passive"))
    )
    (net (code "4") (name "ADC_FM") (class "Default")
      (node (ref "C46") (pin "2") (pinfunction "2_2") (pintype "passive"))
      (node (ref "IC1") (pin "21") (pinfunction "PE8/SDADC1_AIN8P/SDADC2_AIN8P_21") (pintype "bidirectional"))
      (node (ref "IC7") (pin "7") (pinfunction "OUT_7") (pintype "output"))
      (node (ref "R52") (pin "1") (pinfunction "1_1") (pintype "passive"))
    )
    (net (code "5") (name "ADC_SHAPE") (class "Default")
      (node (ref "C32") (pin "2") (pinfunction "2_2") (pintype "passive"))
      (node (ref "IC1") (pin "27") (pinfunction "PB15/SPI2_MOSI/I2S2_SD/SDADC3_AIN7P/SDADC3_AIN8M_27") (pintype "bidirectional"))
      (node (ref "IC6") (pin "8") (pinfunction "OUT_8") (pintype "output"))
      (node (ref "R27") (pin "1") (pinfunction "1_1") (pintype "passive"))
    )
    (net (code "6") (name "ADC_SHIFT") (class "Default")
      (node (ref "C28") (pin "2") (pinfunction "2_2") (pintype "passive"))
      (node (ref "IC1") (pin "28") (pinfunction "PD8/SPI2_SCK/I2S2_CK/USART3_TX/SDADC3_AIN6P_28") (pintype "bidirectional"))
      (node (ref "IC6") (pin "14") (pinfunction "OUT_14") (pintype "output"))
      (node (ref "R19") (pin "1") (pinfunction "1_1") (pintype "passive"))
    )
    (net (code "7") (name "ADC_SLOPE") (class "Default")
      (node (ref "C27") (pin "2") (pinfunction "2_2") (pintype "passive"))
      (node (ref "IC1") (pin "18") (pinfunction "PB0/SPI1_MOSI/I2S1_SD/TIM3_CH3/ADC_IN8/SDADC1_AIN6P_18") (pintype "bidirectional"))
      (node (ref "IC6") (pin "1") (pinfunction "OUT_1") (pintype "output"))
      (node (ref "R18") (pin "1") (pinfunction "1_1") (pintype "passive"))
    )
    (net (code "8") (name "ADC_SMOOTHNESS") (class "Default")
      (node (ref "C41") (pin "2") (pinfunction "2_2") (pintype "passive"))
      (node (ref "IC1") (pin "26") (pinfunction "PB14/SPI2_MISO/I2S2_MCK/USART3_RTS/SDADC3_AIN8P_26") (pintype "bidirectional"))
      (node (ref "IC7") (pin "14") (pinfunction "OUT_14") (pintype "output"))
      (node (ref "R41") (pin "1") (pinfunction "1_1") (pintype "passive"))
    )
    (net (code "9") (name "ADC_TRIG") (class "Default")
      (node (ref "C31") (pin "2") (pinfunction "2_2") (pintype "passive"))
      (node (ref "IC1") (pin "19") (pinfunction "PB1/TIM3_CH4/ADC_IN9/SDADC1_AIN5P/SDADC1_AIN6M_19") (pintype "bidirectional"))
      (node (ref "IC6") (pin "7") (pinfunction "OUT_7") (pintype "output"))
      (node (ref "R28") (pin "1") (pinfunction "1_1") (pintype "passive"))
    )
    (net (code "10") (name "ADC_V_OCT") (class "Default")
      (node (ref "C47") (pin "2") (pinfunction "2_2") (pintype "passive"))
      (node (ref "IC1") (pin "22") (pinfunction "PE9/SDADC1_AIN7P/SDADC1_AIN8M/SDADC2_AIN7P/SDADC2_AIN8M_22") (pintype "bidirectional"))
      (node (ref "IC7") (pin "8") (pinfunction "OUT_8") (pintype "output"))
      (node (ref "R53") (pin "1") (pinfunction "1_1") (pintype "passive"))
    )
    (net (code "11") (name "AREF_-10") (class "Default")
      (node (ref "C42") (pin "1") (pinfunction "1_1") (pintype "passive"))
      (node (ref "IC10") (pin "2") (pinfunction "A_2") (pintype "passive"))
      (node (ref "R20") (pin "2") (pinfunction "2_2") (pintype "passive"))
      (node (ref "R21") (pin "2") (pinfunction "2_2") (pintype "passive"))
      (node (ref "R25") (pin "2") (pinfunction "2_2") (pintype "passive"))
      (node (ref "R26") (pin "2") (pinfunction "2_2") (pintype "passive"))
      (node (ref "R43") (pin "2") (pinfunction "2_2") (pintype "passive"))
      (node (ref "R44") (pin "2") (pinfunction "2_2") (pintype "passive"))
      (node (ref "R46") (pin "2") (pinfunction "2_2") (pintype "passive"))
      (node (ref "R50") (pin "2") (pinfunction "2_2") (pintype "passive"))
      (node (ref "R51") (pin "2") (pinfunction "2_2") (pintype "passive"))
    )
    (net (code "12") (name "DAC_1") (class "Default")
      (node (ref "IC4") (pin "1") (pinfunction "OUTA_1") (pintype "output"))
      (node (ref "R31") (pin "2") (pinfunction "2_2") (pintype "passive"))
    )
    (net (code "13") (name "DAC_2") (class "Default")
      (node (ref "IC4") (pin "2") (pinfunction "OUTB_2") (pintype "output"))
      (node (ref "R32") (pin "2") (pinfunction "2_2") (pintype "passive"))
    )
    (net (code "14") (name "DAC_3") (class "Default")
      (node (ref "IC4") (pin "7") (pinfunction "OUTC_7") (pintype "output"))
      (node (ref "R33") (pin "2") (pinfunction "2_2") (pintype "passive"))
    )
    (net (code "15") (name "DAC_4") (class "Default")
      (node (ref "IC4") (pin "8") (pinfunction "OUTD_8") (pintype "output"))
      (node (ref "R34") (pin "2") (pinfunction "2_2") (pintype "passive"))
    )
    (net (code "16") (name "DAC_MOSI") (class "Default")
      (node (ref "IC1") (pin "31") (pinfunction "PA10/SPI2_MOSI/I2S2_SD/I2C2_SDA/USART1_RX/TIM2_CH4_31") (pintype "bidirectional"))
      (node (ref "IC4") (pin "11") (pinfunction "IN_11") (pintype "input"))
    )
    (net (code "17") (name "DAC_SCK") (class "Default")
      (node (ref "IC1") (pin "29") (pinfunction "PA8/SPI2_SCK/I2S2_CK/I2C2_SMBA/USART1_CK/TIM5_CH1_29") (pintype "bidirectional"))
      (node (ref "IC4") (pin "10") (pinfunction "SCK_10") (pintype "input"))
    )
    (net (code "18") (name "DAC_SS") (class "Default")
      (node (ref "IC1") (pin "32") (pinfunction "PA11/SPI2_NSS/I2S2_WS/SPI1_NSS/I2S1_WS/USART1_CTS/CAN_RX/TIM4_CH1/TIM5_CH2_32") (pintype "bidirectional"))
      (node (ref "IC4") (pin "9") (pinfunction "SYNC_9") (pintype "input"))
    )
    (net (code "19") (name "FREQUENCY_ATT") (class "Default")
      (node (ref "C52") (pin "1") (pinfunction "1_1") (pintype "passive"))
      (node (ref "IC2") (pin "2") (pinfunction "X6_2") (pintype "bidirectional"))
      (node (ref "R57") (pin "P$2") (pinfunction "S_P$2") (pintype "passive"))
    )
    (net (code "20") (name "FREQUENCY_POT") (class "Default")
      (node (ref "C22") (pin "1") (pinfunction "1_1") (pintype "passive"))
      (node (ref "IC1") (pin "16") (pinfunction "PA6/SPI1_MISO/I2S1_MCK/TIM3_CH1/ADC_IN6/DAC2_OUT1_16") (pintype "bidirectional"))
      (node (ref "R11") (pin "P$2") (pinfunction "S_P$2") (pintype "passive"))
    )
    (net (code "21") (name "GND") (class "Default")
      (node (ref "C1") (pin "2") (pinfunction "2_2") (pintype "passive"))
      (node (ref "C10") (pin "-") (pinfunction "-_-") (pintype "passive"))
      (node (ref "C11") (pin "1") (pinfunction "1_1") (pintype "passive"))
      (node (ref "C12") (pin "2") (pinfunction "2_2") (pintype "passive"))
      (node (ref "C13") (pin "2") (pinfunction "2_2") (pintype "passive"))
      (node (ref "C14") (pin "2") (pinfunction "2_2") (pintype "passive"))
      (node (ref "C15") (pin "2") (pinfunction "2_2") (pintype "passive"))
      (node (ref "C16") (pin "2") (pinfunction "2_2") (pintype "passive"))
      (node (ref "C17") (pin "2") (pinfunction "2_2") (pintype "passive"))
      (node (ref "C18") (pin "2") (pinfunction "2_2") (pintype "passive"))
      (node (ref "C19") (pin "2") (pinfunction "2_2") (pintype "passive"))
      (node (ref "C2") (pin "2") (pinfunction "2_2") (pintype "passive"))
      (node (ref "C20") (pin "2") (pinfunction "2_2") (pintype "passive"))
      (node (ref "C21") (pin "2") (pinfunction "2_2") (pintype "passive"))
      (node (ref "C22") (pin "2") (pinfunction "2_2") (pintype "passive"))
      (node (ref "C23") (pin "2") (pinfunction "2_2") (pintype "passive"))
      (node (ref "C24") (pin "-") (pinfunction "-_-") (pintype "passive"))
      (node (ref "C25") (pin "2") (pinfunction "2_2") (pintype "passive"))
      (node (ref "C26") (pin "+") (pinfunction "+_+") (pintype "passive"))
      (node (ref "C29") (pin "-") (pinfunction "-_-") (pintype "passive"))
      (node (ref "C3") (pin "2") (pinfunction "2_2") (pintype "passive"))
      (node (ref "C30") (pin "2") (pinfunction "2_2") (pintype "passive"))
      (node (ref "C33") (pin "1") (pinfunction "1_1") (pintype "passive"))
      (node (ref "C34") (pin "1") (pinfunction "1_1") (pintype "passive"))
      (node (ref "C35") (pin "2") (pinfunction "2_2") (pintype "passive"))
      (node (ref "C4") (pin "1") (pinfunction "1_1") (pintype "passive"))
      (node (ref "C42") (pin "2") (pinfunction "2_2") (pintype "passive"))
      (node (ref "C43") (pin "2") (pinfunction "2_2") (pintype "passive"))
      (node (ref "C44") (pin "2") (pinfunction "2_2") (pintype "passive"))
      (node (ref "C45") (pin "2") (pinfunction "2_2") (pintype "passive"))
      (node (ref "C48") (pin "2") (pinfunction "2_2") (pintype "passive"))
      (node (ref "C49") (pin "2") (pinfunction "2_2") (pintype "passive"))
      (node (ref "C5") (pin "2") (pinfunction "2_2") (pintype "passive"))
      (node (ref "C50") (pin "-") (pinfunction "-_-") (pintype "passive"))
      (node (ref "C51") (pin "2") (pinfunction "2_2") (pintype "passive"))
      (node (ref "C52") (pin "2") (pinfunction "2_2") (pintype "passive"))
      (node (ref "C53") (pin "2") (pinfunction "2_2") (pintype "passive"))
      (node (ref "C54") (pin "2") (pinfunction "2_2") (pintype "passive"))
      (node (ref "C55") (pin "2") (pinfunction "2_2") (pintype "passive"))
      (node (ref "C56") (pin "2") (pinfunction "2_2") (pintype "passive"))
      (node (ref "C6") (pin "2") (pinfunction "2_2") (pintype "passive"))
      (node (ref "C7") (pin "2") (pinfunction "2_2") (pintype "passive"))
      (node (ref "C8") (pin "2") (pinfunction "2_2") (pintype "passive"))
      (node (ref "C9") (pin "-") (pinfunction "-_-") (pintype "passive"))
      (node (ref "D10") (pin "1") (pinfunction "A_1") (pintype "passive"))
      (node (ref "D11") (pin "1") (pinfunction "A_1") (pintype "passive"))
      (node (ref "D2") (pin "1") (pinfunction "A_1") (pintype "passive"))
      (node (ref "D4") (pin "1") (pinfunction "A_1") (pintype "passive"))
      (node (ref "D5") (pin "1") (pinfunction "A_1") (pintype "passive"))
      (node (ref "D6") (pin "1") (pinfunction "A_1") (pintype "passive"))
      (node (ref "D7") (pin "1") (pinfunction "A_1") (pintype "passive"))
      (node (ref "D8") (pin "1") (pinfunction "A_1") (pintype "passive"))
      (node (ref "D9") (pin "1") (pinfunction "A_1") (pintype "passive"))
      (node (ref "IC1") (pin "23") (pinfunction "VSSSD/VREFSD-_23") (pintype "power_in"))
      (node (ref "IC1") (pin "44") (pinfunction "BOOT0_44") (pintype "bidirectional"))
      (node (ref "IC1") (pin "47") (pinfunction "VSS_1_47") (pintype "power_in"))
      (node (ref "IC1") (pin "8") (pinfunction "VSSA_8") (pintype "power_in"))
      (node (ref "IC10") (pin "1") (pinfunction "C_1") (pintype "passive"))
      (node (ref "IC2") (pin "6") (pinfunction "INH_6") (pintype "input"))
      (node (ref "IC2") (pin "7") (pinfunction "VEE_7") (pintype "power_in"))
      (node (ref "IC2") (pin "8") (pinfunction "GND_8") (pintype "power_in"))
      (node (ref "IC3") (pin "2") (pinfunction "GND_2") (pintype "passive"))
      (node (ref "IC4") (pin "13") (pinfunction "A0_13") (pintype "input"))
      (node (ref "IC4") (pin "14") (pinfunction "A1_14") (pintype "input"))
      (node (ref "IC4") (pin "15") (pinfunction "ENABLE_15") (pintype "input"))
      (node (ref "IC4") (pin "16") (pinfunction "LDAC_16") (pintype "input"))
      (node (ref "IC4") (pin "5") (pinfunction "VREFL_5") (pintype "bidirectional"))
      (node (ref "IC4") (pin "6") (pinfunction "GND_6") (pintype "power_in"))
      (node (ref "IC5") (pin "2") (pinfunction "GND_2") (pintype "passive"))
      (node (ref "IC6") (pin "10") (pinfunction "+IN_10") (pintype "input"))
      (node (ref "IC6") (pin "11") (pinfunction "V-_11") (pintype "power_in"))
      (node (ref "IC6") (pin "12") (pinfunction "+IN_12") (pintype "input"))
      (node (ref "IC6") (pin "3") (pinfunction "+IN_3") (pintype "input"))
      (node (ref "IC6") (pin "5") (pinfunction "+IN_5") (pintype "input"))
      (node (ref "IC7") (pin "10") (pinfunction "+IN_10") (pintype "input"))
      (node (ref "IC7") (pin "11") (pinfunction "V-_11") (pintype "power_in"))
      (node (ref "IC7") (pin "12") (pinfunction "+IN_12") (pintype "input"))
      (node (ref "IC7") (pin "3") (pinfunction "+IN_3") (pintype "input"))
      (node (ref "IC7") (pin "5") (pinfunction "+IN_5") (pintype "input"))
      (node (ref "J1") (pin "P1") (pinfunction "1_P1") (pintype "passive"))
      (node (ref "J1") (pin "P2") (pinfunction "2_P2") (pintype "passive"))
      (node (ref "J10") (pin "P1") (pinfunction "1_P1") (pintype "passive"))
      (node (ref "J11") (pin "P1") (pinfunction "1_P1") (pintype "passive"))
      (node (ref "J12") (pin "P1") (pinfunction "1_P1") (pintype "passive"))
      (node (ref "J2") (pin "P1") (pinfunction "1_P1") (pintype "passive"))
      (node (ref "J3") (pin "P1") (pinfunction "1_P1") (pintype "passive"))
      (node (ref "J3") (pin "P2") (pinfunction "2_P2") (pintype "passive"))
      (node (ref "J4") (pin "P1") (pinfunction "1_P1") (pintype "passive"))
      (node (ref "J4") (pin "P2") (pinfunction "2_P2") (pintype "passive"))
      (node (ref "J5") (pin "P1") (pinfunction "1_P1") (pintype "passive"))
      (node (ref "J5") (pin "P2") (pinfunction "2_P2") (pintype "passive"))
      (node (ref "J6") (pin "P1") (pinfunction "1_P1") (pintype "passive"))
      (node (ref "J6") (pin "P2") (pinfunction "2_P2") (pintype "passive"))
      (node (ref "J7") (pin "P1") (pinfunction "1_P1") (pintype "passive"))
      (node (ref "J8") (pin "P1") (pinfunction "1_P1") (pintype "passive"))
      (node (ref "J9") (pin "P1") (pinfunction "1_P1") (pintype "passive"))
      (node (ref "JP5") (pin "3") (pinfunction "3_3") (pintype "passive"))
      (node (ref "JP5") (pin "4") (pinfunction "4_4") (pintype "passive"))
      (node (ref "JP5") (pin "5") (pinfunction "5_5") (pintype "passive"))
      (node (ref "JP5") (pin "6") (pinfunction "6_6") (pintype "passive"))
      (node (ref "JP5") (pin "7") (pinfunction "7_7") (pintype "passive"))
      (node (ref "JP5") (pin "8") (pinfunction "8_8") (pintype "passive"))
      (node (ref "JP6") (pin "1") (pinfunction "1_1") (pintype "passive"))
      (node (ref "LED1") (pin "2") (pinfunction "C_2") (pintype "bidirectional"))
      (node (ref "LED2") (pin "2") (pinfunction "C_2") (pintype "bidirectional"))
      (node (ref "LED3") (pin "2") (pinfunction "C_2") (pintype "bidirectional"))
      (node (ref "Q1") (pin "2") (pinfunction "LID1_2") (pintype "power_in"))
      (node (ref "Q1") (pin "4") (pinfunction "LID2_4") (pintype "power_in"))
      (node (ref "R11") (pin "P$3") (pinfunction "A_P$3") (pintype "passive"))
      (node (ref "R12") (pin "P$3") (pinfunction "A_P$3") (pintype "passive"))
      (node (ref "R15") (pin "1") (pinfunction "1_1") (pintype "passive"))
      (node (ref "R22") (pin "P$3") (pinfunction "A_P$3") (pintype "passive"))
      (node (ref "R23") (pin "P$3") (pinfunction "A_P$3") (pintype "passive"))
      (node (ref "R24") (pin "P$3") (pinfunction "A_P$3") (pintype "passive"))
      (node (ref "R56") (pin "P$3") (pinfunction "A_P$3") (pintype "passive"))
      (node (ref "R57") (pin "P$3") (pinfunction "A_P$3") (pintype "passive"))
      (node (ref "R58") (pin "P$3") (pinfunction "A_P$3") (pintype "passive"))
      (node (ref "R59") (pin "P$3") (pinfunction "A_P$3") (pintype "passive"))
      (node (ref "R60") (pin "P$3") (pinfunction "A_P$3") (pintype "passive"))
      (node (ref "R64") (pin "2") (pinfunction "2_2") (pintype "passive"))
      (node (ref "R65") (pin "2") (pinfunction "2_2") (pintype "passive"))
      (node (ref "R66") (pin "2") (pinfunction "2_2") (pintype "passive"))
      (node (ref "R67") (pin "2") (pinfunction "2_2") (pintype "passive"))
      (node (ref "SW1") (pin "1") (pinfunction "1_1") (pintype "passive"))
      (node (ref "SW1") (pin "2") (pinfunction "2_2") (pintype "passive"))
      (node (ref "SW2") (pin "1") (pinfunction "1_1") (pintype "passive"))
      (node (ref "SW2") (pin "2") (pinfunction "2_2") (pintype "passive"))
      (node (ref "SW3") (pin "1") (pinfunction "1_1") (pintype "passive"))
      (node (ref "SW3") (pin "2") (pinfunction "2_2") (pintype "passive"))
    )
    (net (code "22") (name "LED_MODE_G") (class "Default")
      (node (ref "IC1") (pin "35") (pinfunction "PF6/SPI1_MOSI/I2S1_SD/USART3_RTS/TIM4_CH4/I2C2_SCL_35") (pintype "bidirectional"))
      (node (ref "R10") (pin "1") (pinfunction "1_1") (pintype "passive"))
    )
    (net (code "23") (name "LED_MODE_R") (class "Default")
      (node (ref "IC1") (pin "36") (pinfunction "PF7/I2C2_SDA/USART2_CK_36") (pintype "bidirectional"))
      (node (ref "R13") (pin "1") (pinfunction "1_1") (pintype "passive"))
    )
    (net (code "24") (name "LED_RANGE_G") (class "Default")
      (node (ref "IC1") (pin "42") (pinfunction "PB6/I2C1_SCL/USART1_TX/TIM4_CH1_42") (pintype "bidirectional"))
      (node (ref "R6") (pin "1") (pinfunction "1_1") (pintype "passive"))
    )
    (net (code "25") (name "LED_RANGE_R") (class "Default")
      (node (ref "IC1") (pin "41") (pinfunction "PB5/SPI1_MOSI/I2S1_SD/SPI3_MOSI/I2S3_SD/I2C1_SMBAI/USART2_CK/TIM3_CH2_41") (pintype "bidirectional"))
      (node (ref "R1") (pin "1") (pinfunction "1_1") (pintype "passive"))
    )
    (net (code "26") (name "LED_SHIFT_G") (class "Default")
      (node (ref "IC1") (pin "40") (pinfunction "PB4/SPI1_MISO/I2S1_MCK/SPI3_MISO/I2S3_MCK/USART2_RX/TIM3_CH1/NJTRST_40") (pintype "bidirectional"))
      (node (ref "R2") (pin "1") (pinfunction "1_1") (pintype "passive"))
    )
    (net (code "27") (name "LED_SHIFT_R") (class "Default")
      (node (ref "IC1") (pin "39") (pinfunction "PB3/SPI1_SCK/I2S1_CK/SPI3_SCK/I2S3_CK/USART2_TX/TIM2_CH2/JTDO/SPI3_SCK/JTDO_39") (pintype "bidirectional"))
      (node (ref "R7") (pin "1") (pinfunction "1_1") (pintype "passive"))
    )
    (net (code "28") (name "MUXED_POTS") (class "Default")
      (node (ref "C56") (pin "1") (pinfunction "1_1") (pintype "passive"))
      (node (ref "IC1") (pin "11") (pinfunction "PA1/SPI3_SCK/I2S3_CK/USART2_RTS/TIM2_CH2/TIM5_CH2/ADC_IN1_11") (pintype "bidirectional"))
      (node (ref "IC2") (pin "3") (pinfunction "X_3") (pintype "bidirectional"))
    )
    (net (code "29") (name "MUX_ADDR_0") (class "Default")
      (node (ref "IC1") (pin "13") (pinfunction "PA3/SPI3_MOSI/I2S3_SD/USART2_RX/TIM2_CH4/TIM5_CH4/ADC_IN3_13") (pintype "bidirectional"))
      (node (ref "IC2") (pin "11") (pinfunction "A_11") (pintype "input"))
    )
    (net (code "30") (name "MUX_ADDR_1") (class "Default")
      (node (ref "IC1") (pin "14") (pinfunction "PA4/SPI1_NSS/I2S1_WS/SPI3_NSS/I2S3_WS/USART2_CK/TIM3_CH2/ADC_IN4/DAC1_OUT1_14") (pintype "bidirectional"))
      (node (ref "IC2") (pin "10") (pinfunction "B_10") (pintype "input"))
    )
    (net (code "31") (name "MUX_ADDR_2") (class "Default")
      (node (ref "IC1") (pin "15") (pinfunction "PA5/SPI1_SCK/I2S1_CK/TIM2_CH1/ADC_IN5/DAC1_OUT2_15") (pintype "bidirectional"))
      (node (ref "IC2") (pin "9") (pinfunction "C_9") (pintype "input"))
    )
    (net (code "32") (name "NORMALIZATION_PROBE") (class "Default")
      (node (ref "D2") (pin "3") (pinfunction "AC_3") (pintype "passive"))
      (node (ref "IC1") (pin "30") (pinfunction "PA9/SPI_MISO/I2S2_MCK/I2C2_SCL/USART1_TX/TIM2_CH3_30") (pintype "bidirectional"))
      (node (ref "R61") (pin "2") (pinfunction "2_2") (pintype "passive"))
      (node (ref "R62") (pin "2") (pinfunction "2_2") (pintype "passive"))
      (node (ref "R63") (pin "2") (pinfunction "2_2") (pintype "passive"))
    )
    (net (code "33") (name "Net-(C11-Pad2)") (class "Default")
      (node (ref "C11") (pin "2") (pinfunction "2_2") (pintype "passive"))
      (node (ref "Q1") (pin "1") (pinfunction "1_1") (pintype "passive"))
      (node (ref "R9") (pin "2") (pinfunction "2_2") (pintype "passive"))
    )
    (net (code "34") (name "Net-(C20-Pad1)") (class "Default")
      (node (ref "C20") (pin "1") (pinfunction "1_1") (pintype "passive"))
      (node (ref "D1") (pin "C") (pinfunction "C_C") (pintype "passive"))
      (node (ref "L1") (pin "1") (pinfunction "1_1") (pintype "passive"))
      (node (ref "L2") (pin "2") (pinfunction "2_2") (pintype "passive"))
      (node (ref "L3") (pin "2") (pinfunction "2_2") (pintype "passive"))
    )
    (net (code "35") (name "Net-(D1-PadA)") (class "Default")
      (node (ref "D1") (pin "A") (pinfunction "A_A") (pintype "passive"))
      (node (ref "JP5") (pin "10") (pinfunction "10_10") (pintype "passive"))
      (node (ref "JP5") (pin "9") (pinfunction "9_9") (pintype "passive"))
    )
    (net (code "36") (name "Net-(D3-PadA)") (class "Default")
      (node (ref "D3") (pin "A") (pinfunction "A_A") (pintype "passive"))
      (node (ref "L4") (pin "2") (pinfunction "2_2") (pintype "passive"))
    )
    (net (code "37") (name "Net-(D3-PadC)") (class "Default")
      (node (ref "D3") (pin "C") (pinfunction "C_C") (pintype "passive"))
      (node (ref "JP5") (pin "1") (pinfunction "1_1") (pintype "passive"))
      (node (ref "JP5") (pin "2") (pinfunction "2_2") (pintype "passive"))
    )
    (net (code "38") (name "Net-(D4-C)") (class "Default")
      (node (ref "D4") (pin "2") (pinfunction "C_2") (pintype "passive"))
      (node (ref "J5") (pin "P3") (pinfunction "3_P3") (pintype "passive"))
      (node (ref "R30") (pin "2") (pinfunction "2_2") (pintype "passive"))
    )
    (net (code "39") (name "Net-(D5-C)") (class "Default")
      (node (ref "D5") (pin "2") (pinfunction "C_2") (pintype "passive"))
      (node (ref "J6") (pin "P3") (pinfunction "3_P3") (pintype "passive"))
      (node (ref "R17") (pin "2") (pinfunction "2_2") (pintype "passive"))
    )
    (net (code "40") (name "Net-(D6-C)") (class "Default")
      (node (ref "D6") (pin "2") (pinfunction "C_2") (pintype "passive"))
      (node (ref "J4") (pin "P3") (pinfunction "3_P3") (pintype "passive"))
      (node (ref "R36") (pin "2") (pinfunction "2_2") (pintype "passive"))
    )
    (net (code "41") (name "Net-(D7-C)") (class "Default")
      (node (ref "D7") (pin "2") (pinfunction "C_2") (pintype "passive"))
      (node (ref "J3") (pin "P3") (pinfunction "3_P3") (pintype "passive"))
      (node (ref "R54") (pin "2") (pinfunction "2_2") (pintype "passive"))
    )
    (net (code "42") (name "Net-(D8-C)") (class "Default")
      (node (ref "D8") (pin "2") (pinfunction "C_2") (pintype "passive"))
      (node (ref "J1") (pin "P3") (pinfunction "3_P3") (pintype "passive"))
      (node (ref "R16") (pin "2") (pinfunction "2_2") (pintype "passive"))
    )
    (net (code "43") (name "Net-(D9-C)") (class "Default")
      (node (ref "D9") (pin "2") (pinfunction "C_2") (pintype "passive"))
      (node (ref "J2") (pin "P3") (pinfunction "3_P3") (pintype "passive"))
      (node (ref "R55") (pin "2") (pinfunction "2_2") (pintype "passive"))
    )
    (net (code "44") (name "Net-(D10-C)") (class "Default")
      (node (ref "D10") (pin "2") (pinfunction "C_2") (pintype "passive"))
      (node (ref "J7") (pin "P3") (pinfunction "3_P3") (pintype "passive"))
      (node (ref "R29") (pin "2") (pinfunction "2_2") (pintype "passive"))
    )
    (net (code "45") (name "Net-(D11-C)") (class "Default")
      (node (ref "D11") (pin "2") (pinfunction "C_2") (pintype "passive"))
      (node (ref "J8") (pin "P3") (pinfunction "3_P3") (pintype "passive"))
      (node (ref "R35") (pin "2") (pinfunction "2_2") (pintype "passive"))
    )
    (net (code "46") (name "Net-(IC1-PF0{slash}OSC_IN{slash}I2C2_SDA)") (class "Default")
      (node (ref "IC1") (pin "5") (pinfunction "PF0/OSC_IN/I2C2_SDA_5") (pintype "bidirectional"))
      (node (ref "R8") (pin "1") (pinfunction "1_1") (pintype "passive"))
    )
    (net (code "47") (name "Net-(IC1-PF1{slash}OSC_OUT{slash}I2C2_SCL)") (class "Default")
      (node (ref "IC1") (pin "6") (pinfunction "PF1/OSC_OUT/I2C2_SCL_6") (pintype "bidirectional"))
      (node (ref "R9") (pin "1") (pinfunction "1_1") (pintype "passive"))
    )
    (net (code "48") (name "Net-(IC3-VI)") (class "Default")
      (node (ref "C19") (pin "1") (pinfunction "1_1") (pintype "passive"))
      (node (ref "IC3") (pin "1") (pinfunction "VI_1") (pintype "input"))
      (node (ref "L1") (pin "2") (pinfunction "2_2") (pintype "passive"))
    )
    (net (code "49") (name "Net-(IC5-VI)") (class "Default")
      (node (ref "C25") (pin "1") (pinfunction "1_1") (pintype "passive"))
      (node (ref "IC5") (pin "3") (pinfunction "VI_3") (pintype "input"))
      (node (ref "L3") (pin "1") (pinfunction "1_1") (pintype "passive"))
    )
    (net (code "50") (name "Net-(IC6A--IN)") (class "Default")
      (node (ref "C27") (pin "1") (pinfunction "1_1") (pintype "passive"))
      (node (ref "IC6") (pin "2") (pinfunction "-IN_2") (pintype "input"))
      (node (ref "R16") (pin "1") (pinfunction "1_1") (pintype "passive"))
      (node (ref "R18") (pin "2") (pinfunction "2_2") (pintype "passive"))
      (node (ref "R20") (pin "1") (pinfunction "1_1") (pintype "passive"))
    )
    (net (code "51") (name "Net-(IC6B--IN)") (class "Default")
      (node (ref "C31") (pin "1") (pinfunction "1_1") (pintype "passive"))
      (node (ref "IC6") (pin "6") (pinfunction "-IN_6") (pintype "input"))
      (node (ref "R26") (pin "1") (pinfunction "1_1") (pintype "passive"))
      (node (ref "R28") (pin "2") (pinfunction "2_2") (pintype "passive"))
      (node (ref "R29") (pin "1") (pinfunction "1_1") (pintype "passive"))
    )
    (net (code "52") (name "Net-(IC6C--IN)") (class "Default")
      (node (ref "C32") (pin "1") (pinfunction "1_1") (pintype "passive"))
      (node (ref "IC6") (pin "9") (pinfunction "-IN_9") (pintype "input"))
      (node (ref "R25") (pin "1") (pinfunction "1_1") (pintype "passive"))
      (node (ref "R27") (pin "2") (pinfunction "2_2") (pintype "passive"))
      (node (ref "R30") (pin "1") (pinfunction "1_1") (pintype "passive"))
    )
    (net (code "53") (name "Net-(IC6D--IN)") (class "Default")
      (node (ref "C28") (pin "1") (pinfunction "1_1") (pintype "passive"))
      (node (ref "IC6") (pin "13") (pinfunction "-IN_13") (pintype "input"))
      (node (ref "R17") (pin "1") (pinfunction "1_1") (pintype "passive"))
      (node (ref "R19") (pin "2") (pinfunction "2_2") (pintype "passive"))
      (node (ref "R21") (pin "1") (pinfunction "1_1") (pintype "passive"))
    )
    (net (code "54") (name "Net-(IC7A--IN)") (class "Default")
      (node (ref "C36") (pin "1") (pinfunction "1_1") (pintype "passive"))
      (node (ref "IC7") (pin "2") (pinfunction "-IN_2") (pintype "input"))
      (node (ref "R35") (pin "1") (pinfunction "1_1") (pintype "passive"))
      (node (ref "R37") (pin "2") (pinfunction "2_2") (pintype "passive"))
      (node (ref "R44") (pin "1") (pinfunction "1_1") (pintype "passive"))
    )
    (net (code "55") (name "Net-(IC7B--IN)") (class "Default")
      (node (ref "C46") (pin "1") (pinfunction "1_1") (pintype "passive"))
      (node (ref "IC7") (pin "6") (pinfunction "-IN_6") (pintype "input"))
      (node (ref "R51") (pin "1") (pinfunction "1_1") (pintype "passive"))
      (node (ref "R52") (pin "2") (pinfunction "2_2") (pintype "passive"))
      (node (ref "R55") (pin "1") (pinfunction "1_1") (pintype "passive"))
    )
    (net (code "56") (name "Net-(IC7C--IN)") (class "Default")
      (node (ref "C47") (pin "1") (pinfunction "1_1") (pintype "passive"))
      (node (ref "IC7") (pin "9") (pinfunction "-IN_9") (pintype "input"))
      (node (ref "R50") (pin "1") (pinfunction "1_1") (pintype "passive"))
      (node (ref "R53") (pin "2") (pinfunction "2_2") (pintype "passive"))
      (node (ref "R54") (pin "1") (pinfunction "1_1") (pintype "passive"))
    )
    (net (code "57") (name "Net-(IC7D--IN)") (class "Default")
      (node (ref "C41") (pin "1") (pinfunction "1_1") (pintype "passive"))
      (node (ref "IC7") (pin "13") (pinfunction "-IN_13") (pintype "input"))
      (node (ref "R36") (pin "1") (pinfunction "1_1") (pintype "passive"))
      (node (ref "R41") (pin "2") (pinfunction "2_2") (pintype "passive"))
      (node (ref "R43") (pin "1") (pinfunction "1_1") (pintype "passive"))
    )
    (net (code "58") (name "Net-(IC8A-+IN)") (class "Default")
      (node (ref "C39") (pin "2") (pinfunction "2_2") (pintype "passive"))
      (node (ref "IC8") (pin "14") (pinfunction "OUT_14") (pintype "output"))
      (node (ref "IC8") (pin "3") (pinfunction "+IN_3") (pintype "input"))
      (node (ref "R48") (pin "2") (pinfunction "2_2") (pintype "passive"))
    )
    (net (code "59") (name "Net-(IC8A--IN)") (class "Default")
      (node (ref "IC8") (pin "2") (pinfunction "-IN_2") (pintype "input"))
      (node (ref "LED6") (pin "2") (pinfunction "2_2") (pintype "bidirectional"))
      (node (ref "R66") (pin "1") (pinfunction "1_1") (pintype "passive"))
    )
    (net (code "60") (name "Net-(IC8A-OUT)") (class "Default")
      (node (ref "IC8") (pin "1") (pinfunction "OUT_1") (pintype "output"))
      (node (ref "LED6") (pin "1") (pinfunction "1_1") (pintype "bidirectional"))
    )
    (net (code "61") (name "Net-(IC8B-+IN)") (class "Default")
      (node (ref "C40") (pin "2") (pinfunction "2_2") (pintype "passive"))
      (node (ref "IC8") (pin "5") (pinfunction "+IN_5") (pintype "input"))
      (node (ref "IC8") (pin "8") (pinfunction "OUT_8") (pintype "output"))
      (node (ref "R49") (pin "2") (pinfunction "2_2") (pintype "passive"))
    )
    (net (code "62") (name "Net-(IC8B--IN)") (class "Default")
      (node (ref "IC8") (pin "6") (pinfunction "-IN_6") (pintype "input"))
      (node (ref "LED7") (pin "2") (pinfunction "2_2") (pintype "bidirectional"))
      (node (ref "R67") (pin "1") (pinfunction "1_1") (pintype "passive"))
    )
    (net (code "63") (name "Net-(IC8B-OUT)") (class "Default")
      (node (ref "IC8") (pin "7") (pinfunction "OUT_7") (pintype "output"))
      (node (ref "LED7") (pin "1") (pinfunction "1_1") (pintype "bidirectional"))
    )
    (net (code "64") (name "Net-(IC8C--IN)") (class "Default")
      (node (ref "C40") (pin "1") (pinfunction "1_1") (pintype "passive"))
      (node (ref "IC8") (pin "9") (pinfunction "-IN_9") (pintype "input"))
      (node (ref "R34") (pin "1") (pinfunction "1_1") (pintype "passive"))
      (node (ref "R40") (pin "2") (pinfunction "2_2") (pintype "passive"))
    )
    (net (code "65") (name "Net-(IC8D--IN)") (class "Default")
      (node (ref "C39") (pin "1") (pinfunction "1_1") (pintype "passive"))
      (node (ref "IC8") (pin "13") (pinfunction "-IN_13") (pintype "input"))
      (node (ref "R33") (pin "1") (pinfunction "1_1") (pintype "passive"))
      (node (ref "R39") (pin "2") (pinfunction "2_2") (pintype "passive"))
    )
    (net (code "66") (name "Net-(IC9A-+IN)") (class "Default")
      (node (ref "C37") (pin "2") (pinfunction "2_2") (pintype "passive"))
      (node (ref "IC9") (pin "14") (pinfunction "OUT_14") (pintype "output"))
      (node (ref "IC9") (pin "3") (pinfunction "+IN_3") (pintype "input"))
      (node (ref "R47") (pin "2") (pinfunction "2_2") (pintype "passive"))
    )
    (net (code "67") (name "Net-(IC9A--IN)") (class "Default")
      (node (ref "IC9") (pin "2") (pinfunction "-IN_2") (pintype "input"))
      (node (ref "LED4") (pin "2") (pinfunction "2_2") (pintype "bidirectional"))
      (node (ref "R64") (pin "1") (pinfunction "1_1") (pintype "passive"))
    )
    (net (code "68") (name "Net-(IC9A-OUT)") (class "Default")
      (node (ref "IC9") (pin "1") (pinfunction "OUT_1") (pintype "output"))
      (node (ref "LED4") (pin "1") (pinfunction "1_1") (pintype "bidirectional"))
    )
    (net (code "69") (name "Net-(IC9B-+IN)") (class "Default")
      (node (ref "C38") (pin "2") (pinfunction "2_2") (pintype "passive"))
      (node (ref "IC9") (pin "5") (pinfunction "+IN_5") (pintype "input"))
      (node (ref "IC9") (pin "8") (pinfunction "OUT_8") (pintype "output"))
      (node (ref "R45") (pin "2") (pinfunction "2_2") (pintype "passive"))
    )
    (net (code "70") (name "Net-(IC9B--IN)") (class "Default")
      (node (ref "IC9") (pin "6") (pinfunction "-IN_6") (pintype "input"))
      (node (ref "LED5") (pin "2") (pinfunction "2_2") (pintype "bidirectional"))
      (node (ref "R65") (pin "1") (pinfunction "1_1") (pintype "passive"))
    )
    (net (code "71") (name "Net-(IC9B-OUT)") (class "Default")
      (node (ref "IC9") (pin "7") (pinfunction "OUT_7") (pintype "output"))
      (node (ref "LED5") (pin "1") (pinfunction "1_1") (pintype "bidirectional"))
    )
    (net (code "72") (name "Net-(IC9C--IN)") (class "Default")
      (node (ref "C38") (pin "1") (pinfunction "1_1") (pintype "passive"))
      (node (ref "IC9") (pin "9") (pinfunction "-IN_9") (pintype "input"))
      (node (ref "R32") (pin "1") (pinfunction "1_1") (pintype "passive"))
      (node (ref "R38") (pin "2") (pinfunction "2_2") (pintype "passive"))
    )
    (net (code "73") (name "Net-(IC9D--IN)") (class "Default")
      (node (ref "C37") (pin "1") (pinfunction "1_1") (pintype "passive"))
      (node (ref "IC9") (pin "13") (pinfunction "-IN_13") (pintype "input"))
      (node (ref "R31") (pin "1") (pinfunction "1_1") (pintype "passive"))
      (node (ref "R42") (pin "2") (pinfunction "2_2") (pintype "passive"))
    )
    (net (code "74") (name "Net-(J2-2)") (class "Default")
      (node (ref "J2") (pin "P2") (pinfunction "2_P2") (pintype "passive"))
      (node (ref "R61") (pin "1") (pinfunction "1_1") (pintype "passive"))
    )
    (net (code "75") (name "Net-(J7-2)") (class "Default")
      (node (ref "J7") (pin "P2") (pinfunction "2_P2") (pintype "passive"))
      (node (ref "R62") (pin "1") (pinfunction "1_1") (pintype "passive"))
    )
    (net (code "76") (name "Net-(J8-2)") (class "Default")
      (node (ref "J8") (pin "P2") (pinfunction "2_P2") (pintype "passive"))
      (node (ref "R63") (pin "1") (pinfunction "1_1") (pintype "passive"))
    )
    (net (code "77") (name "Net-(J9-3)") (class "Default")
      (node (ref "J9") (pin "P3") (pinfunction "3_P3") (pintype "passive"))
      (node (ref "R42") (pin "1") (pinfunction "1_1") (pintype "passive"))
      (node (ref "R47") (pin "1") (pinfunction "1_1") (pintype "passive"))
    )
    (net (code "78") (name "Net-(J10-3)") (class "Default")
      (node (ref "J10") (pin "P3") (pinfunction "3_P3") (pintype "passive"))
      (node (ref "R38") (pin "1") (pinfunction "1_1") (pintype "passive"))
      (node (ref "R45") (pin "1") (pinfunction "1_1") (pintype "passive"))
    )
    (net (code "79") (name "Net-(J11-3)") (class "Default")
      (node (ref "J11") (pin "P3") (pinfunction "3_P3") (pintype "passive"))
      (node (ref "R39") (pin "1") (pinfunction "1_1") (pintype "passive"))
      (node (ref "R48") (pin "1") (pinfunction "1_1") (pintype "passive"))
    )
    (net (code "80") (name "Net-(J12-3)") (class "Default")
      (node (ref "J12") (pin "P3") (pinfunction "3_P3") (pintype "passive"))
      (node (ref "R40") (pin "1") (pinfunction "1_1") (pintype "passive"))
      (node (ref "R49") (pin "1") (pinfunction "1_1") (pintype "passive"))
    )
    (net (code "81") (name "Net-(JP7-Pad1)") (class "Default")
      (node (ref "JP7") (pin "1") (pinfunction "1_1") (pintype "passive"))
      (node (ref "R4") (pin "1") (pinfunction "1_1") (pintype "passive"))
    )
    (net (code "82") (name "Net-(JP7-Pad2)") (class "Default")
      (node (ref "JP7") (pin "2") (pinfunction "2_2") (pintype "passive"))
      (node (ref "R5") (pin "1") (pinfunction "1_1") (pintype "passive"))
    )
    (net (code "83") (name "Net-(LED1-GRN)") (class "Default")
      (node (ref "LED1") (pin "1") (pinfunction "GRN_1") (pintype "bidirectional"))
      (node (ref "R6") (pin "2") (pinfunction "2_2") (pintype "passive"))
    )
    (net (code "84") (name "Net-(LED1-RED)") (class "Default")
      (node (ref "LED1") (pin "3") (pinfunction "RED_3") (pintype "bidirectional"))
      (node (ref "R1") (pin "2") (pinfunction "2_2") (pintype "passive"))
    )
    (net (code "85") (name "Net-(LED2-GRN)") (class "Default")
      (node (ref "LED2") (pin "1") (pinfunction "GRN_1") (pintype "bidirectional"))
      (node (ref "R2") (pin "2") (pinfunction "2_2") (pintype "passive"))
    )
    (net (code "86") (name "Net-(LED2-RED)") (class "Default")
      (node (ref "LED2") (pin "3") (pinfunction "RED_3") (pintype "bidirectional"))
      (node (ref "R7") (pin "2") (pinfunction "2_2") (pintype "passive"))
    )
    (net (code "87") (name "Net-(LED3-GRN)") (class "Default")
      (node (ref "LED3") (pin "1") (pinfunction "GRN_1") (pintype "bidirectional"))
      (node (ref "R10") (pin "2") (pinfunction "2_2") (pintype "passive"))
    )
    (net (code "88") (name "Net-(LED3-RED)") (class "Default")
      (node (ref "LED3") (pin "3") (pinfunction "RED_3") (pintype "bidirectional"))
      (node (ref "R13") (pin "2") (pinfunction "2_2") (pintype "passive"))
    )
    (net (code "89") (name "Net-(Q1B-2)") (class "Default")
      (node (ref "C4") (pin "2") (pinfunction "2_2") (pintype "passive"))
      (node (ref "Q1") (pin "3") (pinfunction "2_3") (pintype "passive"))
      (node (ref "R8") (pin "2") (pinfunction "2_2") (pintype "passive"))
    )
    (net (code "90") (name "RESET") (class "Default")
      (node (ref "C2") (pin "1") (pinfunction "1_1") (pintype "passive"))
      (node (ref "IC1") (pin "7") (pinfunction "NRST_7") (pintype "bidirectional"))
      (node (ref "JP6") (pin "4") (pinfunction "4_4") (pintype "passive"))
      (node (ref "R3") (pin "2") (pinfunction "2_2") (pintype "passive"))
    )
    (net (code "91") (name "RX") (class "Default")
      (node (ref "IC1") (pin "46") (pinfunction "PB9/SPI2_NSS/I2S2_WS/I2C1_SDA/USART3_RX/CAN_TX/TIM4_CH4_46") (pintype "bidirectional"))
      (node (ref "R4") (pin "2") (pinfunction "2_2") (pintype "passive"))
    )
    (net (code "92") (name "SHAPE_ATT") (class "Default")
      (node (ref "C54") (pin "1") (pinfunction "1_1") (pintype "passive"))
      (node (ref "IC2") (pin "4") (pinfunction "X7_4") (pintype "bidirectional"))
      (node (ref "R59") (pin "P$2") (pinfunction "S_P$2") (pintype "passive"))
    )
    (net (code "93") (name "SHAPE_POT") (class "Default")
      (node (ref "C23") (pin "1") (pinfunction "1_1") (pintype "passive"))
      (node (ref "IC1") (pin "10") (pinfunction "PA0/USART2_CTS/TIM2_CH1/TIM5_CH1/ADC_IN0_10") (pintype "bidirectional"))
      (node (ref "R12") (pin "P$2") (pinfunction "S_P$2") (pintype "passive"))
    )
    (net (code "94") (name "SHIFT_ATT") (class "Default")
      (node (ref "C55") (pin "1") (pinfunction "1_1") (pintype "passive"))
      (node (ref "IC2") (pin "15") (pinfunction "X2_15") (pintype "bidirectional"))
      (node (ref "R60") (pin "P$2") (pinfunction "S_P$2") (pintype "passive"))
    )
    (net (code "95") (name "SHIFT_POT") (class "Default")
      (node (ref "C45") (pin "1") (pinfunction "1_1") (pintype "passive"))
      (node (ref "IC2") (pin "14") (pinfunction "X1_14") (pintype "bidirectional"))
      (node (ref "R24") (pin "P$2") (pinfunction "S_P$2") (pintype "passive"))
    )
    (net (code "96") (name "SLOPE_ATT") (class "Default")
      (node (ref "C51") (pin "1") (pinfunction "1_1") (pintype "passive"))
      (node (ref "IC2") (pin "1") (pinfunction "X4_1") (pintype "bidirectional"))
      (node (ref "R56") (pin "P$2") (pinfunction "S_P$2") (pintype "passive"))
    )
    (net (code "97") (name "SLOPE_POT") (class "Default")
      (node (ref "C44") (pin "1") (pinfunction "1_1") (pintype "passive"))
      (node (ref "IC2") (pin "12") (pinfunction "X3_12") (pintype "bidirectional"))
      (node (ref "R23") (pin "P$2") (pinfunction "S_P$2") (pintype "passive"))
    )
    (net (code "98") (name "SMOOTHNESS_ATT") (class "Default")
      (node (ref "C53") (pin "1") (pinfunction "1_1") (pintype "passive"))
      (node (ref "IC2") (pin "5") (pinfunction "X5_5") (pintype "bidirectional"))
      (node (ref "R58") (pin "P$2") (pinfunction "S_P$2") (pintype "passive"))
    )
    (net (code "99") (name "SMOOTHNESS_POT") (class "Default")
      (node (ref "C35") (pin "1") (pinfunction "1_1") (pintype "passive"))
      (node (ref "IC2") (pin "13") (pinfunction "X0_13") (pintype "bidirectional"))
      (node (ref "R22") (pin "P$2") (pinfunction "S_P$2") (pintype "passive"))
    )
    (net (code "100") (name "SWCLK") (class "Default")
      (node (ref "IC1") (pin "37") (pinfunction "PA14/I2C1_SDA/JTCK-SWCLK_37") (pintype "bidirectional"))
      (node (ref "JP6") (pin "3") (pinfunction "3_3") (pintype "passive"))
    )
    (net (code "101") (name "SWDIO") (class "Default")
      (node (ref "IC1") (pin "34") (pinfunction "PA13/SPI1_MISO/I2S1_MCK/USART3_CTS/TIM4_CH3/TIM5_CH4/JTMS-SWDIO_34") (pintype "bidirectional"))
      (node (ref "JP6") (pin "2") (pinfunction "2_2") (pintype "passive"))
    )
    (net (code "102") (name "SW_MODE") (class "Default")
      (node (ref "IC1") (pin "33") (pinfunction "PA12/SPI1_SCK/I2S1_CK/USART1_RTS/CAN_TX/TIM4_CH2/TIM5_CH3_33") (pintype "bidirectional"))
      (node (ref "SW3") (pin "3") (pinfunction "3_3") (pintype "passive"))
      (node (ref "SW3") (pin "4") (pinfunction "4_4") (pintype "passive"))
    )
    (net (code "103") (name "SW_RANGE") (class "Default")
      (node (ref "IC1") (pin "12") (pinfunction "PA2/SPI3_MISO/I2S3_MCK/USART2_TX/TIM2_CH3/TIM5_CH3/ADC_IN2_12") (pintype "bidirectional"))
      (node (ref "SW2") (pin "3") (pinfunction "3_3") (pintype "passive"))
      (node (ref "SW2") (pin "4") (pinfunction "4_4") (pintype "passive"))
    )
    (net (code "104") (name "SW_SHIFT") (class "Default")
      (node (ref "IC1") (pin "2") (pinfunction "PC13/TIMESTAMP/RTC_TAMPER1_2") (pintype "bidirectional"))
      (node (ref "SW1") (pin "3") (pinfunction "3_3") (pintype "passive"))
      (node (ref "SW1") (pin "4") (pinfunction "4_4") (pintype "passive"))
    )
    (net (code "105") (name "TX") (class "Default")
      (node (ref "IC1") (pin "45") (pinfunction "PB8/SPI2_SCK/I2S2_CK/I2C1_SCL/USART3_TX/CAN_RX/TIM4_CH3_45") (pintype "bidirectional"))
      (node (ref "R5") (pin "2") (pinfunction "2_2") (pintype "passive"))
    )
    (net (code "106") (name "VCC") (class "Default")
      (node (ref "C24") (pin "+") (pinfunction "+_+") (pintype "passive"))
      (node (ref "C48") (pin "1") (pinfunction "1_1") (pintype "passive"))
      (node (ref "C49") (pin "1") (pinfunction "1_1") (pintype "passive"))
      (node (ref "IC8") (pin "4") (pinfunction "V+_4") (pintype "power_in"))
      (node (ref "IC9") (pin "4") (pinfunction "V+_4") (pintype "power_in"))
      (node (ref "L2") (pin "1") (pinfunction "1_1") (pintype "passive"))
    )
    (net (code "107") (name "VEE") (class "Default")
      (node (ref "C26") (pin "-") (pinfunction "-_-") (pintype "passive"))
      (node (ref "C33") (pin "2") (pinfunction "2_2") (pintype "passive"))
      (node (ref "C34") (pin "2") (pinfunction "2_2") (pintype "passive"))
      (node (ref "IC8") (pin "11") (pinfunction "V-_11") (pintype "power_in"))
      (node (ref "IC9") (pin "11") (pinfunction "V-_11") (pintype "power_in"))
      (node (ref "L4") (pin "1") (pinfunction "1_1") (pintype "passive"))
      (node (ref "R46") (pin "1") (pinfunction "1_1") (pintype "passive"))
    )
    (net (code "108") (name "VREF") (class "Default")
      (node (ref "C18") (pin "1") (pinfunction "1_1") (pintype "passive"))
      (node (ref "IC4") (pin "3") (pinfunction "VREFH_3") (pintype "bidirectional"))
      (node (ref "R14") (pin "2") (pinfunction "2_2") (pintype "passive"))
    )
    (net (code "109") (name "VREF_BIAS") (class "Default")
      (node (ref "C21") (pin "1") (pinfunction "1_1") (pintype "passive"))
      (node (ref "IC8") (pin "10") (pinfunction "+IN_10") (pintype "input"))
      (node (ref "IC8") (pin "12") (pinfunction "+IN_12") (pintype "input"))
      (node (ref "IC9") (pin "10") (pinfunction "+IN_10") (pintype "input"))
      (node (ref "IC9") (pin "12") (pinfunction "+IN_12") (pintype "input"))
      (node (ref "R14") (pin "1") (pinfunction "1_1") (pintype "passive"))
      (node (ref "R15") (pin "2") (pinfunction "2_2") (pintype "passive"))
    )
    (net (code "110") (name "unconnected-(IC1-PA15{slash}SPI1_NSS{slash}I2S1_WS{slash}SPI3_NSS{slash}I2S3_WS{slash}I2C1_SCL{slash}TIM2_CH1_ETR{slash}JTDI-Pad38)") (class "Default")
      (node (ref "IC1") (pin "38") (pinfunction "PA15/SPI1_NSS/I2S1_WS/SPI3_NSS/I2S3_WS/I2C1_SCL/TIM2_CH1_ETR/JTDI_38") (pintype "bidirectional"))
    )
    (net (code "111") (name "unconnected-(IC1-PB7{slash}I2C1_SDA{slash}USART1_RX{slash}TIM4_CH2-Pad43)") (class "Default")
      (node (ref "IC1") (pin "43") (pinfunction "PB7/I2C1_SDA/USART1_RX/TIM4_CH2_43") (pintype "bidirectional"))
    )
    (net (code "112") (name "unconnected-(IC1-PC14{slash}OSC32_IN-Pad3)") (class "Default")
      (node (ref "IC1") (pin "3") (pinfunction "PC14/OSC32_IN_3") (pintype "bidirectional"))
    )
    (net (code "113") (name "unconnected-(IC1-PC15{slash}OSC32_OUT-Pad4)") (class "Default")
      (node (ref "IC1") (pin "4") (pinfunction "PC15/OSC32_OUT_4") (pintype "bidirectional"))
    )
    (net (code "114") (name "unconnected-(J9-2-PadP2)") (class "Default")
      (node (ref "J9") (pin "P2") (pinfunction "2_P2") (pintype "passive"))
    )
    (net (code "115") (name "unconnected-(J10-2-PadP2)") (class "Default")
      (node (ref "J10") (pin "P2") (pinfunction "2_P2") (pintype "passive"))
    )
    (net (code "116") (name "unconnected-(J11-2-PadP2)") (class "Default")
      (node (ref "J11") (pin "P2") (pinfunction "2_P2") (pintype "passive"))
    )
    (net (code "117") (name "unconnected-(J12-2-PadP2)") (class "Default")
      (node (ref "J12") (pin "P2") (pinfunction "2_P2") (pintype "passive"))
    )
  )
)
